# M7106B.net
KiCad netlist of a schematic drawn in EAGLE
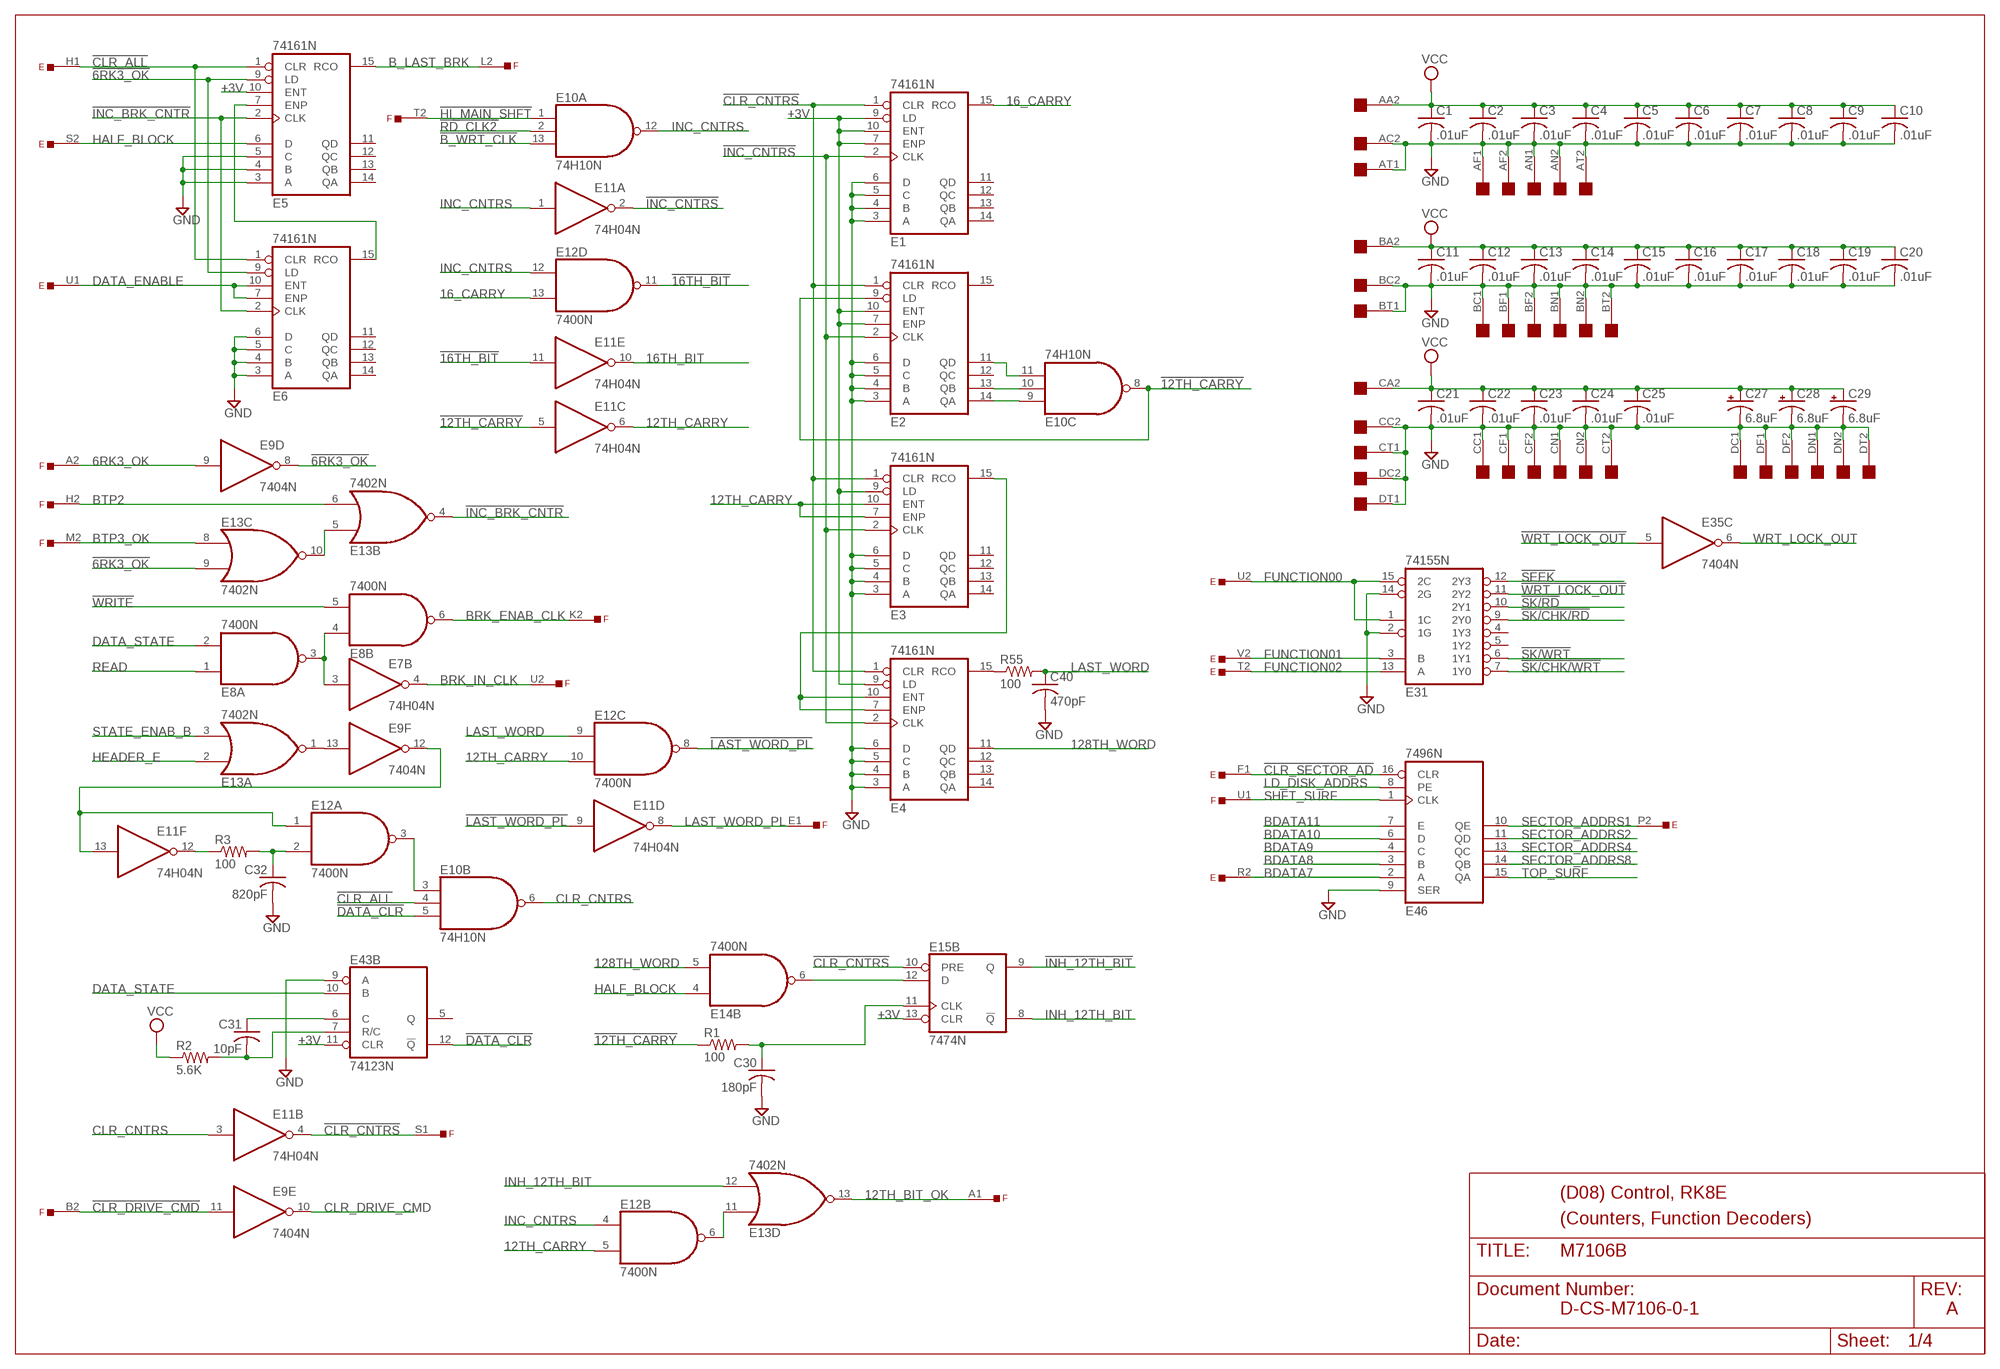
[diagram p0: schematic, sheet 1]
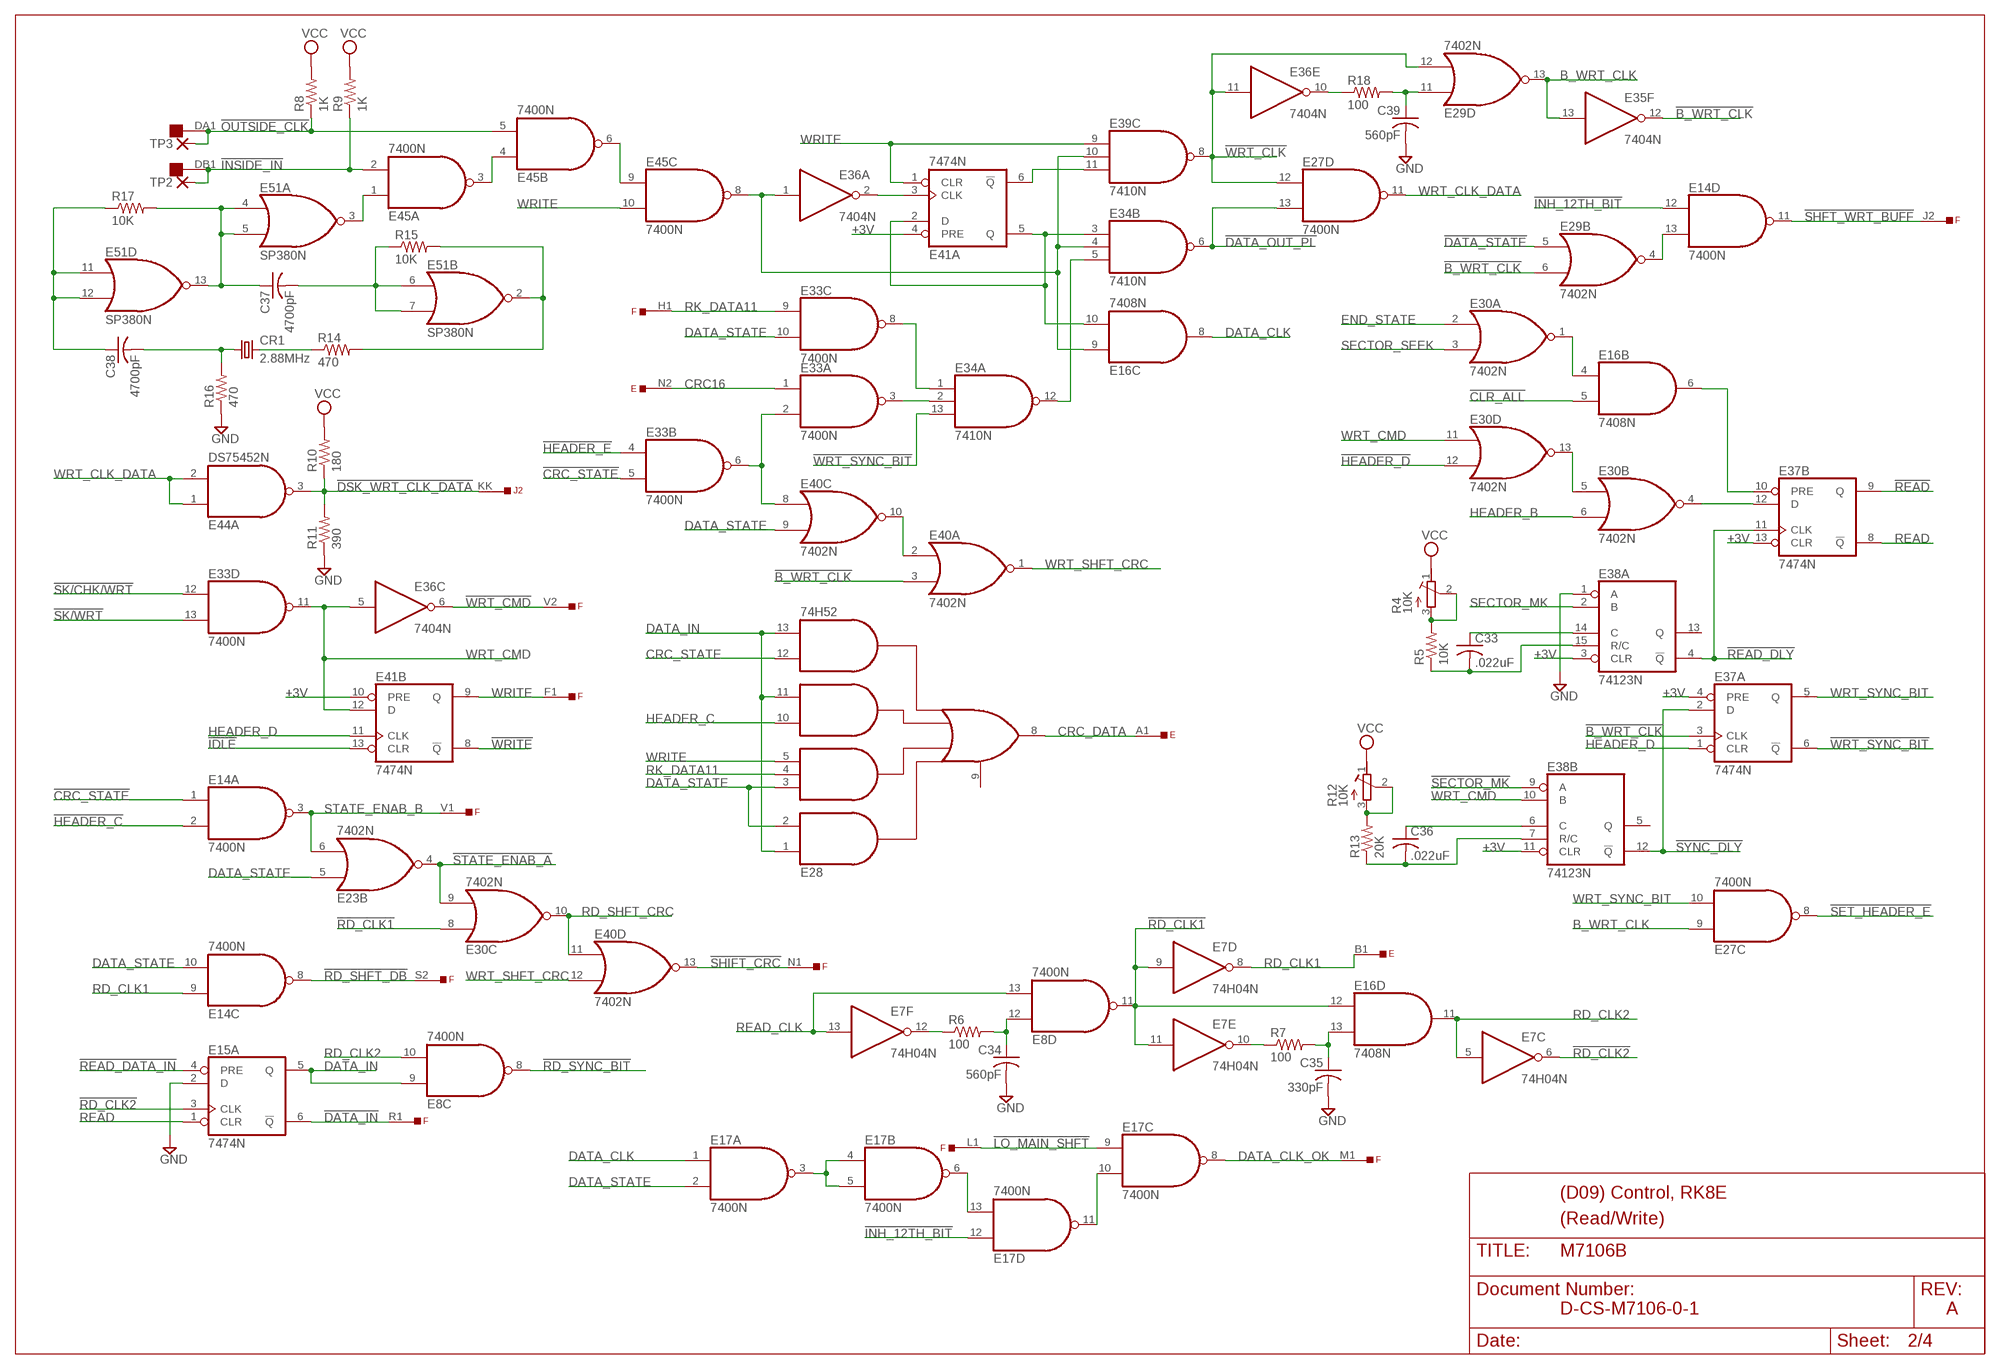
[diagram p1: schematic, sheet 2]
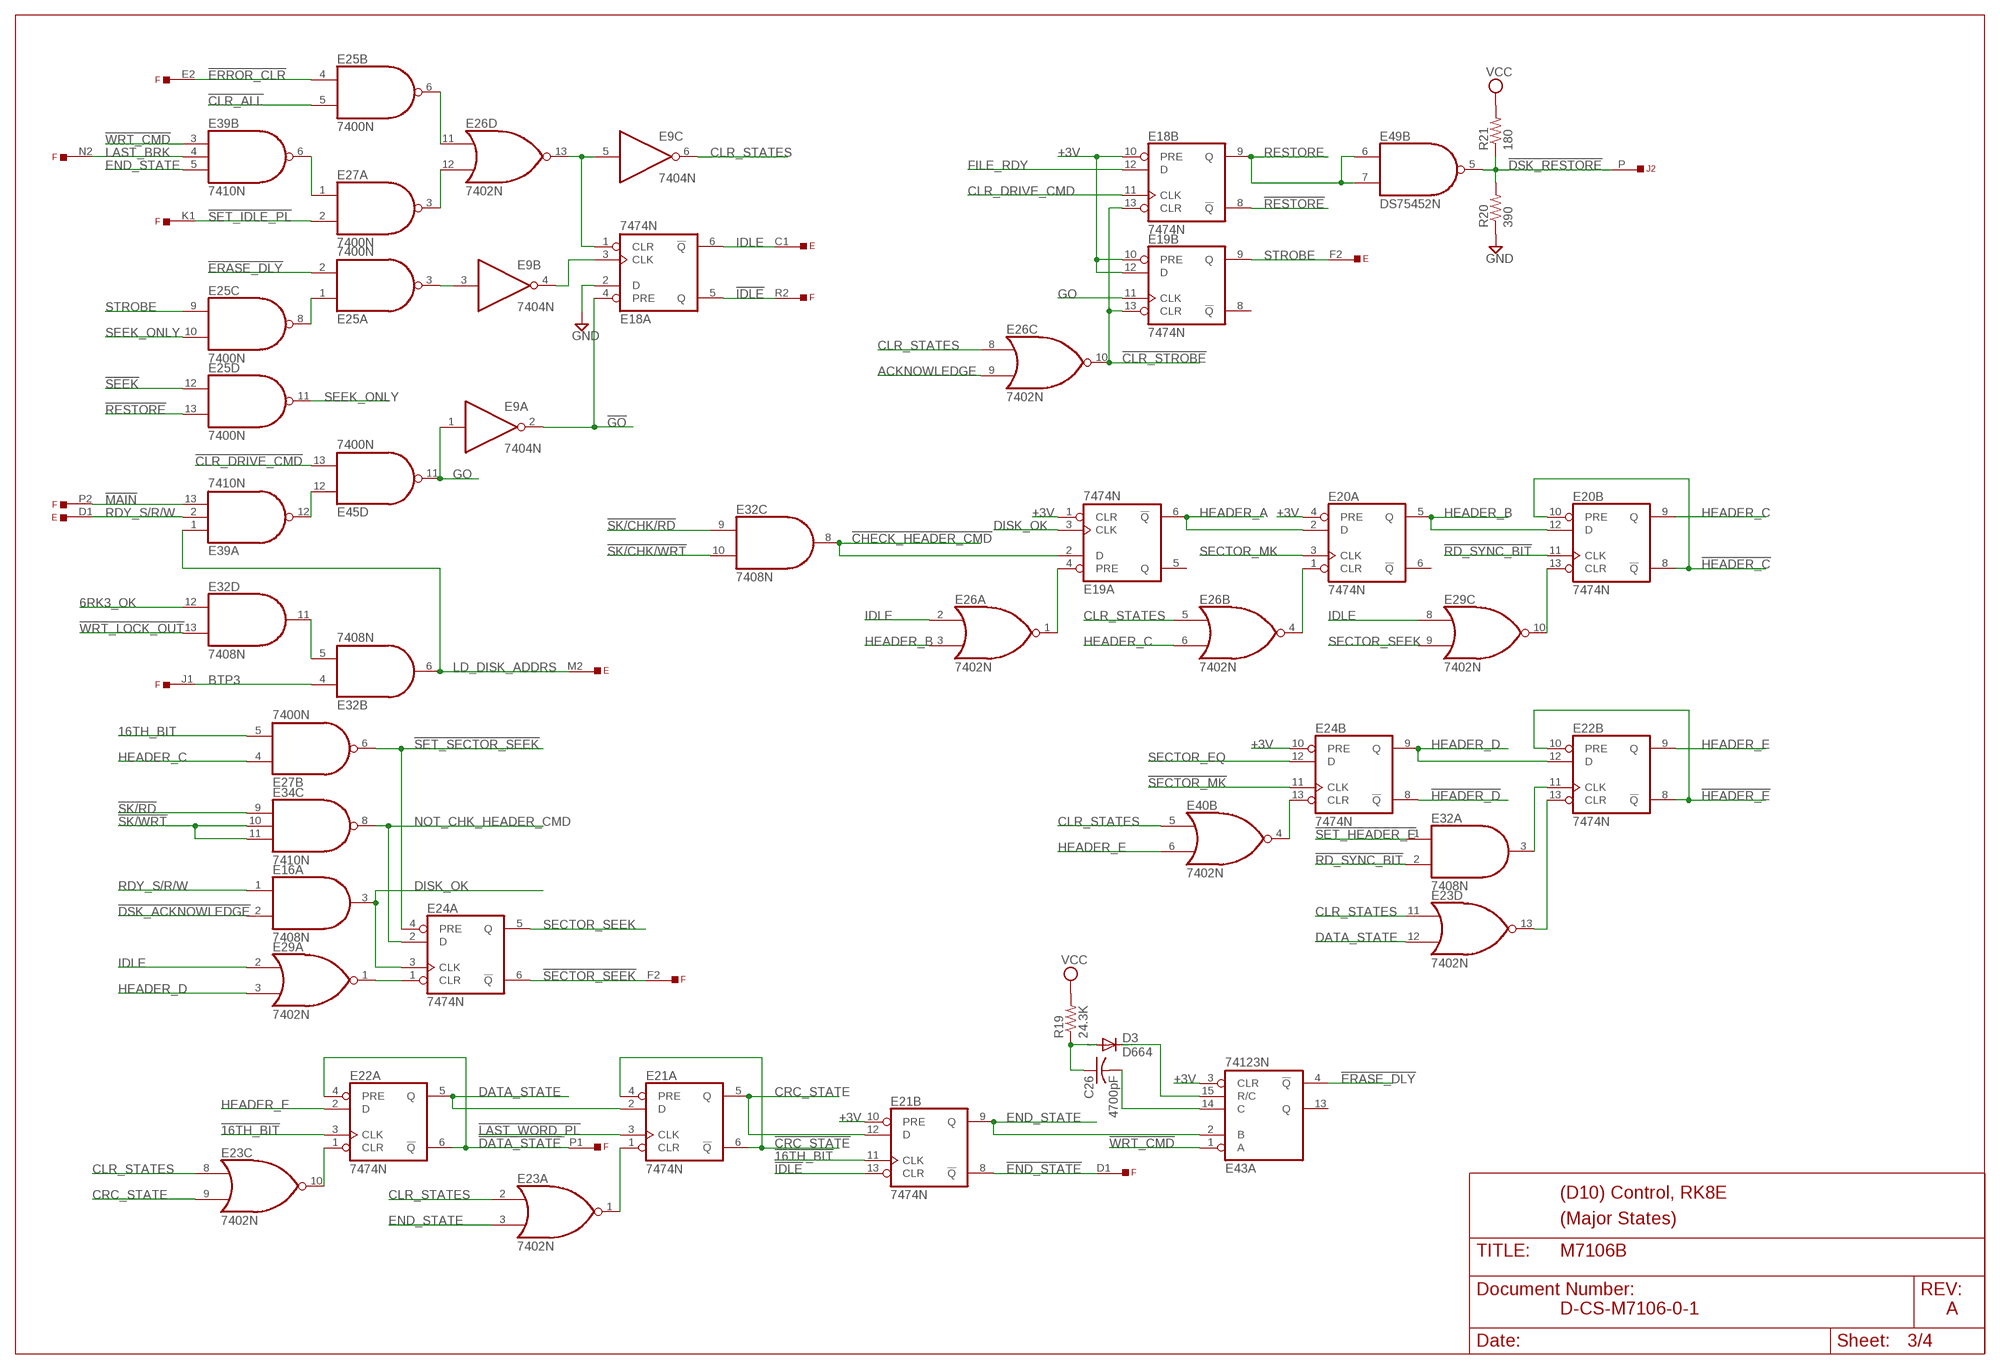
[diagram p2: schematic, sheet 3]
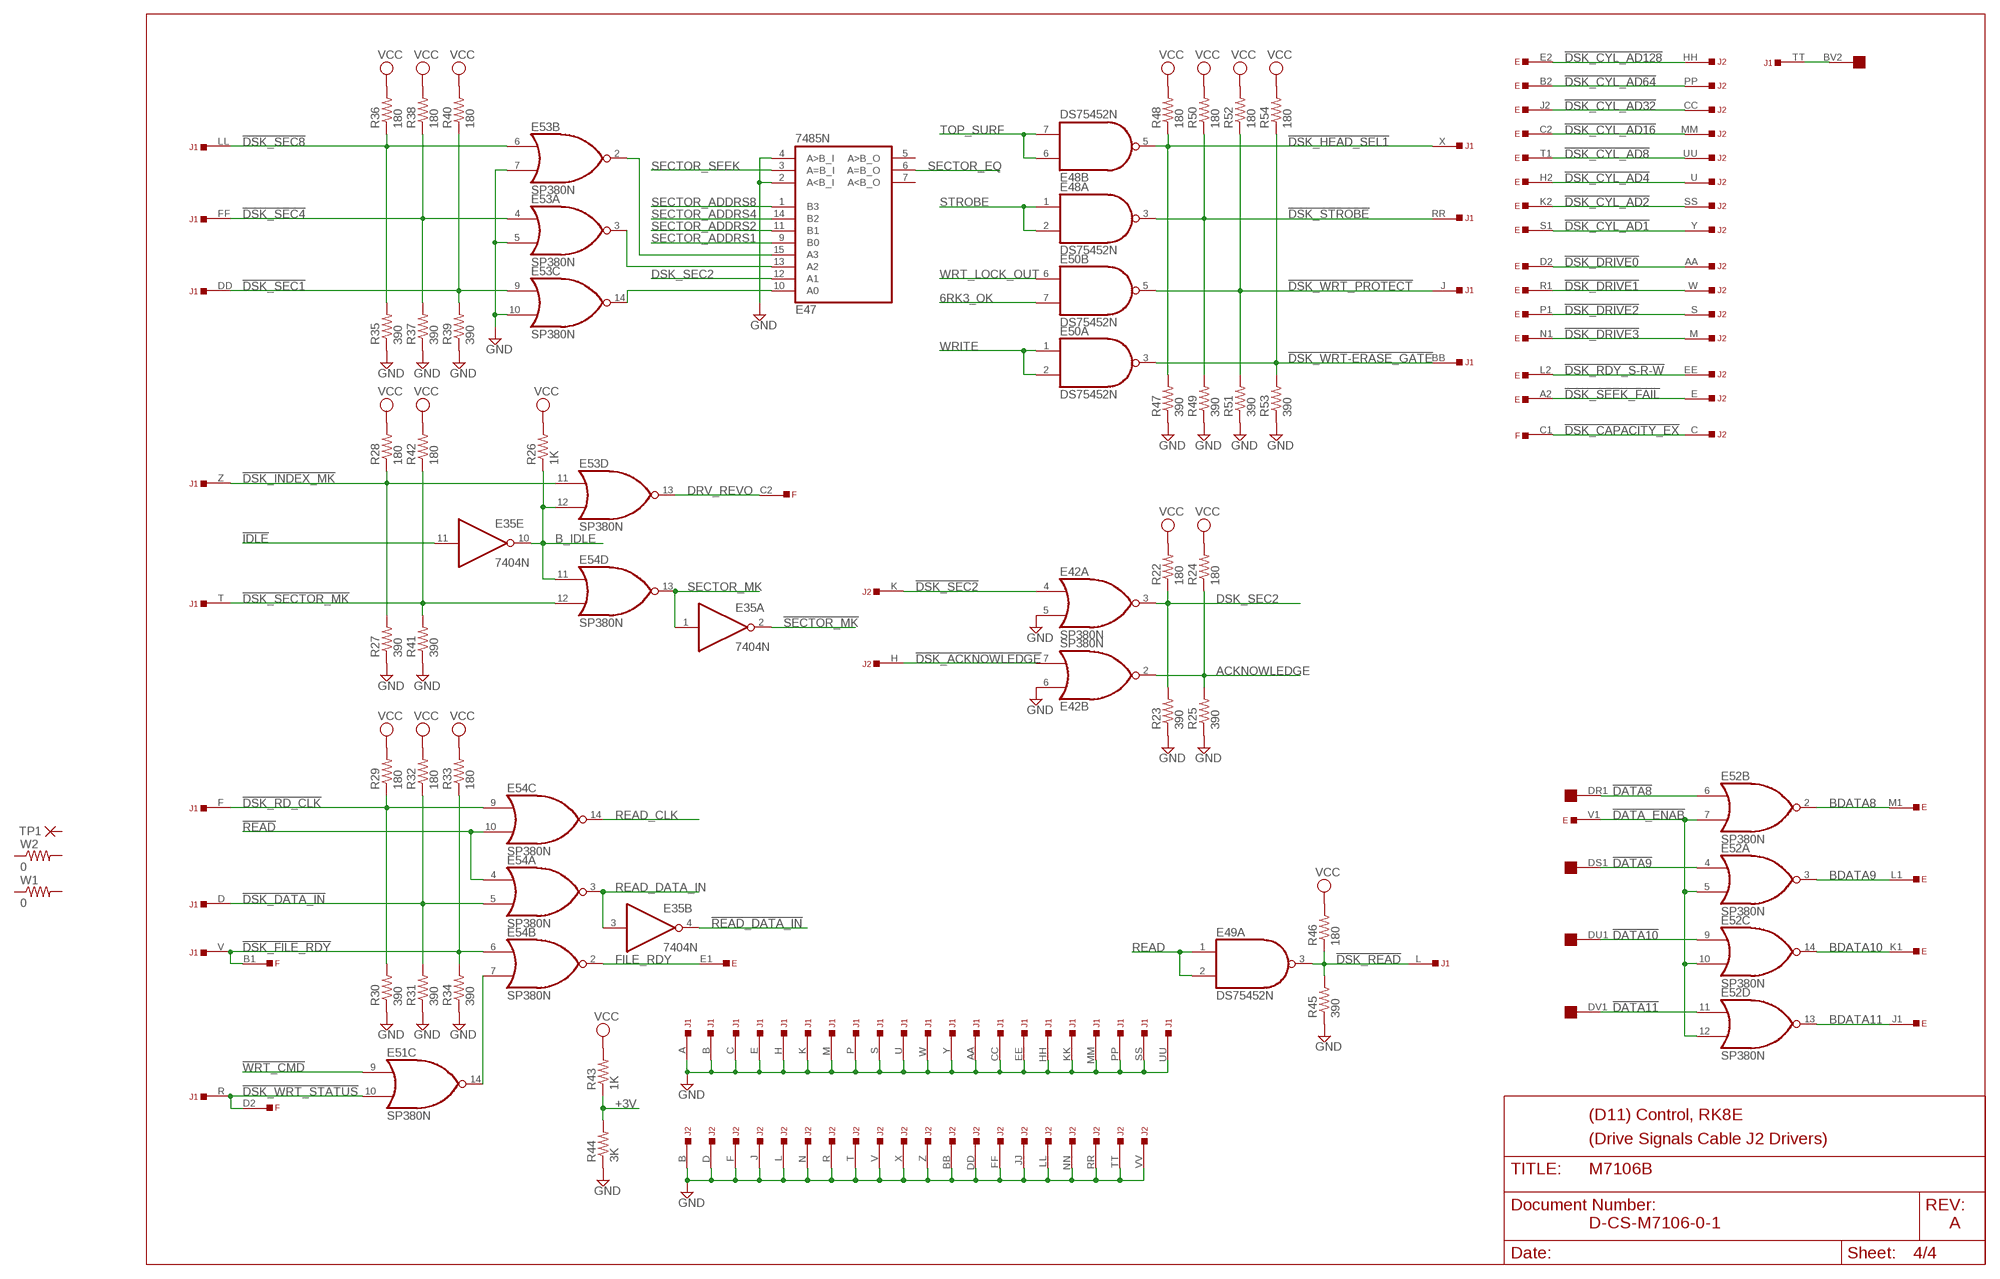
[diagram p3: schematic, sheet 4]

(export (version "E")
  (design (tool "Eeschema 10.0.6"))
  (components
    (comp (ref "C1")
      (value ".01uF")
      (footprint "eagle-import:C063-025X075")
      (libsource (lib "eagle-import") (part "C-US"))
    )
    (comp (ref "C2")
      (value ".01uF")
      (footprint "eagle-import:C063-025X075")
      (libsource (lib "eagle-import") (part "C-US"))
    )
    (comp (ref "C3")
      (value ".01uF")
      (footprint "eagle-import:C063-025X075")
      (libsource (lib "eagle-import") (part "C-US"))
    )
    (comp (ref "C4")
      (value ".01uF")
      (footprint "eagle-import:C063-025X075")
      (libsource (lib "eagle-import") (part "C-US"))
    )
    (comp (ref "C5")
      (value ".01uF")
      (footprint "eagle-import:C063-025X075")
      (libsource (lib "eagle-import") (part "C-US"))
    )
    (comp (ref "C6")
      (value ".01uF")
      (footprint "eagle-import:C063-025X075")
      (libsource (lib "eagle-import") (part "C-US"))
    )
    (comp (ref "C7")
      (value ".01uF")
      (footprint "eagle-import:C063-025X075")
      (libsource (lib "eagle-import") (part "C-US"))
    )
    (comp (ref "C8")
      (value ".01uF")
      (footprint "eagle-import:C063-025X075")
      (libsource (lib "eagle-import") (part "C-US"))
    )
    (comp (ref "C9")
      (value ".01uF")
      (footprint "eagle-import:C063-025X075")
      (libsource (lib "eagle-import") (part "C-US"))
    )
    (comp (ref "C10")
      (value ".01uF")
      (footprint "eagle-import:C063-025X075")
      (libsource (lib "eagle-import") (part "C-US"))
    )
    (comp (ref "C11")
      (value ".01uF")
      (footprint "eagle-import:C063-025X075")
      (libsource (lib "eagle-import") (part "C-US"))
    )
    (comp (ref "C12")
      (value ".01uF")
      (footprint "eagle-import:C063-025X075")
      (libsource (lib "eagle-import") (part "C-US"))
    )
    (comp (ref "C13")
      (value ".01uF")
      (footprint "eagle-import:C063-025X075")
      (libsource (lib "eagle-import") (part "C-US"))
    )
    (comp (ref "C14")
      (value ".01uF")
      (footprint "eagle-import:C063-025X075")
      (libsource (lib "eagle-import") (part "C-US"))
    )
    (comp (ref "C15")
      (value ".01uF")
      (footprint "eagle-import:C063-025X075")
      (libsource (lib "eagle-import") (part "C-US"))
    )
    (comp (ref "C16")
      (value ".01uF")
      (footprint "eagle-import:C063-025X075")
      (libsource (lib "eagle-import") (part "C-US"))
    )
    (comp (ref "C17")
      (value ".01uF")
      (footprint "eagle-import:C063-025X075")
      (libsource (lib "eagle-import") (part "C-US"))
    )
    (comp (ref "C18")
      (value ".01uF")
      (footprint "eagle-import:C063-025X075")
      (libsource (lib "eagle-import") (part "C-US"))
    )
    (comp (ref "C19")
      (value ".01uF")
      (footprint "eagle-import:C063-025X075")
      (libsource (lib "eagle-import") (part "C-US"))
    )
    (comp (ref "C20")
      (value ".01uF")
      (footprint "eagle-import:C063-025X075")
      (libsource (lib "eagle-import") (part "C-US"))
    )
    (comp (ref "C21")
      (value ".01uF")
      (footprint "eagle-import:C063-025X075")
      (libsource (lib "eagle-import") (part "C-US"))
    )
    (comp (ref "C22")
      (value ".01uF")
      (footprint "eagle-import:C063-025X075")
      (libsource (lib "eagle-import") (part "C-US"))
    )
    (comp (ref "C23")
      (value ".01uF")
      (footprint "eagle-import:C063-025X075")
      (libsource (lib "eagle-import") (part "C-US"))
    )
    (comp (ref "C24")
      (value ".01uF")
      (footprint "eagle-import:C063-025X075")
      (libsource (lib "eagle-import") (part "C-US"))
    )
    (comp (ref "C25")
      (value ".01uF")
      (footprint "eagle-import:C063-025X075")
      (libsource (lib "eagle-import") (part "C-US"))
    )
    (comp (ref "C27")
      (value "6.8uF")
      (footprint "eagle-import:E12-8")
      (libsource (lib "eagle-import") (part "CPOL-USE20-8AXIAL"))
    )
    (comp (ref "C28")
      (value "6.8uF")
      (footprint "eagle-import:E12-8")
      (libsource (lib "eagle-import") (part "CPOL-USE20-8AXIAL"))
    )
    (comp (ref "C29")
      (value "6.8uF")
      (footprint "eagle-import:E12-8")
      (libsource (lib "eagle-import") (part "CPOL-USE20-8AXIAL"))
    )
    (comp (ref "C30")
      (value "180pF")
      (footprint "eagle-import:C063-025X075")
      (libsource (lib "eagle-import") (part "C-US"))
    )
    (comp (ref "C31")
      (value "10pF")
      (footprint "eagle-import:C063-025X075")
      (libsource (lib "eagle-import") (part "C-US"))
    )
    (comp (ref "C32")
      (value "820pF")
      (footprint "eagle-import:C063-025X075")
      (libsource (lib "eagle-import") (part "C-US"))
    )
    (comp (ref "C40")
      (value "470pF")
      (footprint "eagle-import:C063-025X075")
      (libsource (lib "eagle-import") (part "C-US"))
    )
    (comp (ref "E")
      (value "EDGE-TOP")
      (footprint "eagle-import:EDGE-CON2")
      (libsource (lib "eagle-import") (part "EDGE-TOP"))
    )
    (comp (ref "E1")
      (value "74161N")
      (footprint "eagle-import:DIL16")
      (libsource (lib "eagle-import") (part "74161N"))
    )
    (comp (ref "E2")
      (value "74161N")
      (footprint "eagle-import:DIL16")
      (libsource (lib "eagle-import") (part "74161N"))
    )
    (comp (ref "E3")
      (value "74161N")
      (footprint "eagle-import:DIL16")
      (libsource (lib "eagle-import") (part "74161N"))
    )
    (comp (ref "E4")
      (value "74161N")
      (footprint "eagle-import:DIL16")
      (libsource (lib "eagle-import") (part "74161N"))
    )
    (comp (ref "E5")
      (value "74161N")
      (footprint "eagle-import:DIL16")
      (libsource (lib "eagle-import") (part "74161N"))
    )
    (comp (ref "E6")
      (value "74161N")
      (footprint "eagle-import:DIL16")
      (libsource (lib "eagle-import") (part "74161N"))
    )
    (comp (ref "E7")
      (value "74H04N")
      (footprint "eagle-import:DIL14")
      (libsource (lib "eagle-import") (part "7404N"))
    )
    (comp (ref "E8")
      (value "7400N")
      (footprint "eagle-import:DIL14")
      (libsource (lib "eagle-import") (part "7400N"))
    )
    (comp (ref "E9")
      (value "7404N")
      (footprint "eagle-import:DIL14")
      (libsource (lib "eagle-import") (part "7404N"))
    )
    (comp (ref "E10")
      (value "74H10N")
      (footprint "eagle-import:DIL14")
      (libsource (lib "eagle-import") (part "7410N"))
    )
    (comp (ref "E11")
      (value "74H04N")
      (footprint "eagle-import:DIL14")
      (libsource (lib "eagle-import") (part "7404N"))
    )
    (comp (ref "E12")
      (value "7400N")
      (footprint "eagle-import:DIL14")
      (libsource (lib "eagle-import") (part "7400N"))
    )
    (comp (ref "E13")
      (value "7402N")
      (footprint "eagle-import:DIL14")
      (libsource (lib "eagle-import") (part "7402N"))
    )
    (comp (ref "E14")
      (value "7400N")
      (footprint "eagle-import:DIL14")
      (libsource (lib "eagle-import") (part "7400N"))
    )
    (comp (ref "E15")
      (value "7474N")
      (footprint "eagle-import:DIL14")
      (libsource (lib "eagle-import") (part "7474NS"))
    )
    (comp (ref "E31")
      (value "74155N")
      (footprint "eagle-import:DIL16")
      (libsource (lib "eagle-import") (part "74155N"))
    )
    (comp (ref "E35")
      (value "7404N")
      (footprint "eagle-import:DIL14")
      (libsource (lib "eagle-import") (part "7404N"))
    )
    (comp (ref "E43")
      (value "74123N")
      (footprint "eagle-import:DIL16")
      (libsource (lib "eagle-import") (part "74123N"))
    )
    (comp (ref "E46")
      (value "7496N")
      (footprint "eagle-import:DIL16")
      (libsource (lib "eagle-import") (part "7496NLS"))
    )
    (comp (ref "F")
      (value "EDGE-TOP")
      (footprint "eagle-import:EDGE-CON2")
      (libsource (lib "eagle-import") (part "EDGE-TOP"))
    )
    (comp (ref "OMNIBUS")
      (value "QUAD")
      (footprint "eagle-import:EDGE-CON8")
      (libsource (lib "eagle-import") (part "QUAD"))
    )
    (comp (ref "R1")
      (value "100")
      (footprint "eagle-import:0207_10")
      (libsource (lib "eagle-import") (part "R-US_0207/10"))
    )
    (comp (ref "R2")
      (value "5.6K")
      (footprint "eagle-import:0207_10")
      (libsource (lib "eagle-import") (part "R-US_0207/10"))
    )
    (comp (ref "R3")
      (value "100")
      (footprint "eagle-import:0207_10")
      (libsource (lib "eagle-import") (part "R-US_0207/10"))
    )
    (comp (ref "R55")
      (value "100")
      (footprint "eagle-import:0207_10")
      (libsource (lib "eagle-import") (part "R-US_0207/10"))
    )
    (comp (ref "C33")
      (value ".022uF")
      (footprint "eagle-import:C203-054-229")
      (libsource (lib "eagle-import") (part "C-US8"))
    )
    (comp (ref "C34")
      (value "560pF")
      (footprint "eagle-import:C063-025X075")
      (libsource (lib "eagle-import") (part "C-US"))
    )
    (comp (ref "C35")
      (value "330pF")
      (footprint "eagle-import:C063-025X075")
      (libsource (lib "eagle-import") (part "C-US"))
    )
    (comp (ref "C36")
      (value ".022uF")
      (footprint "eagle-import:C203-054-229")
      (libsource (lib "eagle-import") (part "C-US8"))
    )
    (comp (ref "C37")
      (value "4700pF")
      (footprint "eagle-import:C203-054-229")
      (libsource (lib "eagle-import") (part "C-US8"))
    )
    (comp (ref "C38")
      (value "4700pF")
      (footprint "eagle-import:C203-054-229")
      (libsource (lib "eagle-import") (part "C-US8"))
    )
    (comp (ref "C39")
      (value "560pF")
      (footprint "eagle-import:C063-025X075")
      (libsource (lib "eagle-import") (part "C-US"))
    )
    (comp (ref "CR1")
      (value "2.88MHz")
      (footprint "eagle-import:HC49TL-H")
      (libsource (lib "eagle-import") (part "CRYSTALHC49TL-H"))
    )
    (comp (ref "E16")
      (value "7408N")
      (footprint "eagle-import:DIL14")
      (libsource (lib "eagle-import") (part "7408NS"))
    )
    (comp (ref "E17")
      (value "7400N")
      (footprint "eagle-import:DIL14")
      (libsource (lib "eagle-import") (part "7400N"))
    )
    (comp (ref "E23")
      (value "7402N")
      (footprint "eagle-import:DIL14")
      (libsource (lib "eagle-import") (part "7402N"))
    )
    (comp (ref "E27")
      (value "7400N")
      (footprint "eagle-import:DIL14")
      (libsource (lib "eagle-import") (part "7400N"))
    )
    (comp (ref "E28")
      (value "74H52")
      (footprint "eagle-import:DIL14")
      (libsource (lib "eagle-import") (part "7452H"))
    )
    (comp (ref "E29")
      (value "7402N")
      (footprint "eagle-import:DIL14")
      (libsource (lib "eagle-import") (part "7402N"))
    )
    (comp (ref "E30")
      (value "7402N")
      (footprint "eagle-import:DIL14")
      (libsource (lib "eagle-import") (part "7402N"))
    )
    (comp (ref "E33")
      (value "7400N")
      (footprint "eagle-import:DIL14")
      (libsource (lib "eagle-import") (part "7400N"))
    )
    (comp (ref "E34")
      (value "7410N")
      (footprint "eagle-import:DIL14")
      (libsource (lib "eagle-import") (part "7410N"))
    )
    (comp (ref "E36")
      (value "7404N")
      (footprint "eagle-import:DIL14")
      (libsource (lib "eagle-import") (part "7404N"))
    )
    (comp (ref "E37")
      (value "7474N")
      (footprint "eagle-import:DIL14")
      (libsource (lib "eagle-import") (part "7474NS"))
    )
    (comp (ref "E38")
      (value "74123N")
      (footprint "eagle-import:DIL16")
      (libsource (lib "eagle-import") (part "74123N"))
    )
    (comp (ref "E39")
      (value "7410N")
      (footprint "eagle-import:DIL14")
      (libsource (lib "eagle-import") (part "7410N"))
    )
    (comp (ref "E40")
      (value "7402N")
      (footprint "eagle-import:DIL14")
      (libsource (lib "eagle-import") (part "7402N"))
    )
    (comp (ref "E41")
      (value "7474N")
      (footprint "eagle-import:DIL14")
      (libsource (lib "eagle-import") (part "7474NS"))
    )
    (comp (ref "E44")
      (value "DS75452N")
      (footprint "eagle-import:DIL08")
      (libsource (lib "eagle-import") (part "DS75452N"))
    )
    (comp (ref "E45")
      (value "7400N")
      (footprint "eagle-import:DIL14")
      (libsource (lib "eagle-import") (part "7400N"))
    )
    (comp (ref "E51")
      (value "SP380N")
      (footprint "eagle-import:DIL14")
      (libsource (lib "eagle-import") (part "SP380N"))
    )
    (comp (ref "J2")
      (value "DEC40PINSH")
      (footprint "eagle-import:DEC40PINH")
      (libsource (lib "eagle-import") (part "DEC40PINSH"))
    )
    (comp (ref "R4")
      (value "10K")
      (footprint "eagle-import:3006Y")
      (libsource (lib "eagle-import") (part "275P"))
    )
    (comp (ref "R5")
      (value "10K")
      (footprint "eagle-import:0207_10")
      (libsource (lib "eagle-import") (part "R-US_0207/10"))
    )
    (comp (ref "R6")
      (value "100")
      (footprint "eagle-import:0207_10")
      (libsource (lib "eagle-import") (part "R-US_0207/10"))
    )
    (comp (ref "R7")
      (value "100")
      (footprint "eagle-import:0207_10")
      (libsource (lib "eagle-import") (part "R-US_0207/10"))
    )
    (comp (ref "R8")
      (value "1K")
      (footprint "eagle-import:0207_10")
      (libsource (lib "eagle-import") (part "R-US_0207/10"))
    )
    (comp (ref "R9")
      (value "1K")
      (footprint "eagle-import:0207_10")
      (libsource (lib "eagle-import") (part "R-US_0207/10"))
    )
    (comp (ref "R10")
      (value "180")
      (footprint "eagle-import:0207_10")
      (libsource (lib "eagle-import") (part "R-US_0207/10"))
    )
    (comp (ref "R11")
      (value "390")
      (footprint "eagle-import:0207_10")
      (libsource (lib "eagle-import") (part "R-US_0207/10"))
    )
    (comp (ref "R12")
      (value "10K")
      (footprint "eagle-import:3006Y")
      (libsource (lib "eagle-import") (part "275P"))
    )
    (comp (ref "R13")
      (value "20K")
      (footprint "eagle-import:0207_10")
      (libsource (lib "eagle-import") (part "R-US_0207/10"))
    )
    (comp (ref "R14")
      (value "470")
      (footprint "eagle-import:0207_10")
      (libsource (lib "eagle-import") (part "R-US_0207/10"))
    )
    (comp (ref "R15")
      (value "10K")
      (footprint "eagle-import:0207_10")
      (libsource (lib "eagle-import") (part "R-US_0207/10"))
    )
    (comp (ref "R16")
      (value "470")
      (footprint "eagle-import:0207_10")
      (libsource (lib "eagle-import") (part "R-US_0207/10"))
    )
    (comp (ref "R17")
      (value "10K")
      (footprint "eagle-import:0207_10")
      (libsource (lib "eagle-import") (part "R-US_0207/10"))
    )
    (comp (ref "R18")
      (value "100")
      (footprint "eagle-import:0207_10")
      (libsource (lib "eagle-import") (part "R-US_0207/10"))
    )
    (comp (ref "TP2")
      (value "PAD-0420")
      (footprint "eagle-import:0420")
      (libsource (lib "eagle-import") (part "PAD-0420"))
    )
    (comp (ref "TP3")
      (value "PAD-0420")
      (footprint "eagle-import:0420")
      (libsource (lib "eagle-import") (part "PAD-0420"))
    )
    (comp (ref "E42")
      (value "SP380N")
      (footprint "eagle-import:DIL14")
      (libsource (lib "eagle-import") (part "SP380N"))
    )
    (comp (ref "E47")
      (value "7485N")
      (footprint "eagle-import:DIL16")
      (libsource (lib "eagle-import") (part "7485N"))
    )
    (comp (ref "E48")
      (value "DS75452N")
      (footprint "eagle-import:DIL08")
      (libsource (lib "eagle-import") (part "DS75452N"))
    )
    (comp (ref "E49")
      (value "DS75452N")
      (footprint "eagle-import:DIL08")
      (libsource (lib "eagle-import") (part "DS75452N"))
    )
    (comp (ref "E50")
      (value "DS75452N")
      (footprint "eagle-import:DIL08")
      (libsource (lib "eagle-import") (part "DS75452N"))
    )
    (comp (ref "E52")
      (value "SP380N")
      (footprint "eagle-import:DIL14")
      (libsource (lib "eagle-import") (part "SP380N"))
    )
    (comp (ref "E53")
      (value "SP380N")
      (footprint "eagle-import:DIL14")
      (libsource (lib "eagle-import") (part "SP380N"))
    )
    (comp (ref "E54")
      (value "SP380N")
      (footprint "eagle-import:DIL14")
      (libsource (lib "eagle-import") (part "SP380N"))
    )
    (comp (ref "J1")
      (value "DEC40PINSH")
      (footprint "eagle-import:DEC40PINH")
      (libsource (lib "eagle-import") (part "DEC40PINSH"))
    )
    (comp (ref "R22")
      (value "180")
      (footprint "eagle-import:0207_10")
      (libsource (lib "eagle-import") (part "R-US_0207/10"))
    )
    (comp (ref "R23")
      (value "390")
      (footprint "eagle-import:0207_10")
      (libsource (lib "eagle-import") (part "R-US_0207/10"))
    )
    (comp (ref "R24")
      (value "180")
      (footprint "eagle-import:0207_10")
      (libsource (lib "eagle-import") (part "R-US_0207/10"))
    )
    (comp (ref "R25")
      (value "390")
      (footprint "eagle-import:0207_10")
      (libsource (lib "eagle-import") (part "R-US_0207/10"))
    )
    (comp (ref "R26")
      (value "1K")
      (footprint "eagle-import:0207_10")
      (libsource (lib "eagle-import") (part "R-US_0207/10"))
    )
    (comp (ref "R27")
      (value "390")
      (footprint "eagle-import:0207_10")
      (libsource (lib "eagle-import") (part "R-US_0207/10"))
    )
    (comp (ref "R28")
      (value "180")
      (footprint "eagle-import:0207_10")
      (libsource (lib "eagle-import") (part "R-US_0207/10"))
    )
    (comp (ref "R29")
      (value "180")
      (footprint "eagle-import:0207_10")
      (libsource (lib "eagle-import") (part "R-US_0207/10"))
    )
    (comp (ref "R30")
      (value "390")
      (footprint "eagle-import:0207_10")
      (libsource (lib "eagle-import") (part "R-US_0207/10"))
    )
    (comp (ref "R31")
      (value "390")
      (footprint "eagle-import:0207_10")
      (libsource (lib "eagle-import") (part "R-US_0207/10"))
    )
    (comp (ref "R32")
      (value "180")
      (footprint "eagle-import:0207_10")
      (libsource (lib "eagle-import") (part "R-US_0207/10"))
    )
    (comp (ref "R33")
      (value "180")
      (footprint "eagle-import:0207_10")
      (libsource (lib "eagle-import") (part "R-US_0207/10"))
    )
    (comp (ref "R34")
      (value "390")
      (footprint "eagle-import:0207_10")
      (libsource (lib "eagle-import") (part "R-US_0207/10"))
    )
    (comp (ref "R35")
      (value "390")
      (footprint "eagle-import:0207_10")
      (libsource (lib "eagle-import") (part "R-US_0207/10"))
    )
    (comp (ref "R36")
      (value "180")
      (footprint "eagle-import:0207_10")
      (libsource (lib "eagle-import") (part "R-US_0207/10"))
    )
    (comp (ref "R37")
      (value "390")
      (footprint "eagle-import:0207_10")
      (libsource (lib "eagle-import") (part "R-US_0207/10"))
    )
    (comp (ref "R38")
      (value "180")
      (footprint "eagle-import:0207_10")
      (libsource (lib "eagle-import") (part "R-US_0207/10"))
    )
    (comp (ref "R39")
      (value "390")
      (footprint "eagle-import:0207_10")
      (libsource (lib "eagle-import") (part "R-US_0207/10"))
    )
    (comp (ref "R40")
      (value "180")
      (footprint "eagle-import:0207_10")
      (libsource (lib "eagle-import") (part "R-US_0207/10"))
    )
    (comp (ref "R41")
      (value "390")
      (footprint "eagle-import:0207_10")
      (libsource (lib "eagle-import") (part "R-US_0207/10"))
    )
    (comp (ref "R42")
      (value "180")
      (footprint "eagle-import:0207_10")
      (libsource (lib "eagle-import") (part "R-US_0207/10"))
    )
    (comp (ref "R43")
      (value "1K")
      (footprint "eagle-import:0207_10")
      (libsource (lib "eagle-import") (part "R-US_0207/10"))
    )
    (comp (ref "R44")
      (value "3K")
      (footprint "eagle-import:0207_10")
      (libsource (lib "eagle-import") (part "R-US_0207/10"))
    )
    (comp (ref "R45")
      (value "390")
      (footprint "eagle-import:0207_10")
      (libsource (lib "eagle-import") (part "R-US_0207/10"))
    )
    (comp (ref "R46")
      (value "180")
      (footprint "eagle-import:0207_10")
      (libsource (lib "eagle-import") (part "R-US_0207/10"))
    )
    (comp (ref "R47")
      (value "390")
      (footprint "eagle-import:0207_10")
      (libsource (lib "eagle-import") (part "R-US_0207/10"))
    )
    (comp (ref "R48")
      (value "180")
      (footprint "eagle-import:0207_10")
      (libsource (lib "eagle-import") (part "R-US_0207/10"))
    )
    (comp (ref "R49")
      (value "390")
      (footprint "eagle-import:0207_10")
      (libsource (lib "eagle-import") (part "R-US_0207/10"))
    )
    (comp (ref "R50")
      (value "180")
      (footprint "eagle-import:0207_10")
      (libsource (lib "eagle-import") (part "R-US_0207/10"))
    )
    (comp (ref "R51")
      (value "390")
      (footprint "eagle-import:0207_10")
      (libsource (lib "eagle-import") (part "R-US_0207/10"))
    )
    (comp (ref "R52")
      (value "180")
      (footprint "eagle-import:0207_10")
      (libsource (lib "eagle-import") (part "R-US_0207/10"))
    )
    (comp (ref "R53")
      (value "390")
      (footprint "eagle-import:0207_10")
      (libsource (lib "eagle-import") (part "R-US_0207/10"))
    )
    (comp (ref "R54")
      (value "180")
      (footprint "eagle-import:0207_10")
      (libsource (lib "eagle-import") (part "R-US_0207/10"))
    )
    (comp (ref "TP1")
      (value "PAD-0420")
      (footprint "eagle-import:0420")
      (libsource (lib "eagle-import") (part "PAD-0420"))
    )
    (comp (ref "W1")
      (value "0")
      (footprint "eagle-import:0207_10")
      (libsource (lib "eagle-import") (part "R-US_0207/10"))
    )
    (comp (ref "W2")
      (value "0")
      (footprint "eagle-import:0207_10")
      (libsource (lib "eagle-import") (part "R-US_0207/10"))
    )
    (comp (ref "C26")
      (value "4700pF")
      (footprint "eagle-import:C203-054-229")
      (libsource (lib "eagle-import") (part "C-US8"))
    )
    (comp (ref "D3")
      (value "D664")
      (footprint "eagle-import:DO35-10")
      (libsource (lib "eagle-import") (part "DIODE-DO35-10"))
    )
    (comp (ref "E18")
      (value "7474N")
      (footprint "eagle-import:DIL14")
      (libsource (lib "eagle-import") (part "7474NS"))
    )
    (comp (ref "E19")
      (value "7474N")
      (footprint "eagle-import:DIL14")
      (libsource (lib "eagle-import") (part "7474NS"))
    )
    (comp (ref "E20")
      (value "7474N")
      (footprint "eagle-import:DIL14")
      (libsource (lib "eagle-import") (part "7474NS"))
    )
    (comp (ref "E21")
      (value "7474N")
      (footprint "eagle-import:DIL14")
      (libsource (lib "eagle-import") (part "7474NS"))
    )
    (comp (ref "E22")
      (value "7474N")
      (footprint "eagle-import:DIL14")
      (libsource (lib "eagle-import") (part "7474NS"))
    )
    (comp (ref "E24")
      (value "7474N")
      (footprint "eagle-import:DIL14")
      (libsource (lib "eagle-import") (part "7474NS"))
    )
    (comp (ref "E25")
      (value "7400N")
      (footprint "eagle-import:DIL14")
      (libsource (lib "eagle-import") (part "7400NS"))
    )
    (comp (ref "E26")
      (value "7402N")
      (footprint "eagle-import:DIL14")
      (libsource (lib "eagle-import") (part "7402N"))
    )
    (comp (ref "E32")
      (value "7408N")
      (footprint "eagle-import:DIL14")
      (libsource (lib "eagle-import") (part "7408NS"))
    )
    (comp (ref "R19")
      (value "24.3K")
      (footprint "eagle-import:0207_15")
      (libsource (lib "eagle-import") (part "R-US_0207/15"))
    )
    (comp (ref "R20")
      (value "390")
      (footprint "eagle-import:0207_10")
      (libsource (lib "eagle-import") (part "R-US_0207/10"))
    )
    (comp (ref "R21")
      (value "180")
      (footprint "eagle-import:0207_10")
      (libsource (lib "eagle-import") (part "R-US_0207/10"))
    )
  )
  (nets
    (net (code "1") (name "+3V") (class "Default")
      (node (ref "E1") (pin "10") (pinfunction "ENT_10") (pintype "input"))
      (node (ref "E1") (pin "7") (pinfunction "ENP_7") (pintype "input"))
      (node (ref "E1") (pin "9") (pinfunction "LD_9") (pintype "input"))
      (node (ref "E15") (pin "13") (pinfunction "CLR_13") (pintype "input"))
      (node (ref "E18") (pin "10") (pinfunction "PRE_10") (pintype "input"))
      (node (ref "E19") (pin "1") (pinfunction "CLR_1") (pintype "input"))
      (node (ref "E19") (pin "10") (pinfunction "PRE_10") (pintype "input"))
      (node (ref "E19") (pin "12") (pinfunction "D_12") (pintype "input"))
      (node (ref "E2") (pin "10") (pinfunction "ENT_10") (pintype "input"))
      (node (ref "E2") (pin "7") (pinfunction "ENP_7") (pintype "input"))
      (node (ref "E20") (pin "4") (pinfunction "PRE_4") (pintype "input"))
      (node (ref "E21") (pin "10") (pinfunction "PRE_10") (pintype "input"))
      (node (ref "E24") (pin "10") (pinfunction "PRE_10") (pintype "input"))
      (node (ref "E3") (pin "9") (pinfunction "LD_9") (pintype "input"))
      (node (ref "E37") (pin "13") (pinfunction "CLR_13") (pintype "input"))
      (node (ref "E37") (pin "4") (pinfunction "PRE_4") (pintype "input"))
      (node (ref "E38") (pin "11") (pinfunction "CLR_11") (pintype "input"))
      (node (ref "E38") (pin "3") (pinfunction "CLR_3") (pintype "input"))
      (node (ref "E4") (pin "9") (pinfunction "LD_9") (pintype "input"))
      (node (ref "E41") (pin "10") (pinfunction "PRE_10") (pintype "input"))
      (node (ref "E41") (pin "4") (pinfunction "PRE_4") (pintype "input"))
      (node (ref "E43") (pin "11") (pinfunction "CLR_11") (pintype "input"))
      (node (ref "E43") (pin "3") (pinfunction "CLR_3") (pintype "input"))
      (node (ref "E5") (pin "10") (pinfunction "ENT_10") (pintype "input"))
      (node (ref "R43") (pin "1") (pinfunction "1_1") (pintype "passive"))
      (node (ref "R44") (pin "2") (pinfunction "2_2") (pintype "passive"))
    )
    (net (code "2") (name "6RK3_OK") (class "Default")
      (node (ref "E32") (pin "12") (pinfunction "I0_12") (pintype "input"))
      (node (ref "E50") (pin "7") (pinfunction "I1_7") (pintype "input"))
      (node (ref "E9") (pin "9") (pinfunction "I_9") (pintype "input"))
      (node (ref "F") (pin "A2") (pinfunction "P_A2") (pintype "passive"))
    )
    (net (code "3") (name "12TH_BIT_OK") (class "Default")
      (node (ref "E13") (pin "13") (pinfunction "O_13") (pintype "output"))
      (node (ref "F") (pin "A1") (pinfunction "P_A1") (pintype "passive"))
    )
    (net (code "4") (name "12TH_CARRY") (class "Default")
      (node (ref "E11") (pin "6") (pinfunction "O_6") (pintype "output"))
      (node (ref "E12") (pin "10") (pinfunction "I1_10") (pintype "input"))
      (node (ref "E12") (pin "5") (pinfunction "I1_5") (pintype "input"))
      (node (ref "E3") (pin "10") (pinfunction "ENT_10") (pintype "input"))
      (node (ref "E3") (pin "7") (pinfunction "ENP_7") (pintype "input"))
    )
    (net (code "5") (name "16TH_BIT") (class "Default")
      (node (ref "E11") (pin "10") (pinfunction "O_10") (pintype "output"))
      (node (ref "E27") (pin "5") (pinfunction "I1_5") (pintype "input"))
    )
    (net (code "6") (name "16_CARRY") (class "Default")
      (node (ref "E1") (pin "15") (pinfunction "RCO_15") (pintype "output"))
      (node (ref "E12") (pin "13") (pinfunction "I1_13") (pintype "input"))
    )
    (net (code "7") (name "128TH_WORD") (class "Default")
      (node (ref "E14") (pin "5") (pinfunction "I1_5") (pintype "input"))
      (node (ref "E4") (pin "11") (pinfunction "QD_11") (pintype "output"))
    )
    (net (code "8") (name "ACKNOWLEDGE") (class "Default")
      (node (ref "E26") (pin "9") (pinfunction "I1_9") (pintype "input"))
      (node (ref "E42") (pin "2") (pinfunction "O_2") (pintype "output"))
      (node (ref "R24") (pin "1") (pinfunction "1_1") (pintype "passive"))
      (node (ref "R25") (pin "2") (pinfunction "2_2") (pintype "passive"))
    )
    (net (code "9") (name "BDATA7") (class "Default")
      (node (ref "E") (pin "R2") (pinfunction "P_R2") (pintype "passive"))
      (node (ref "E46") (pin "2") (pinfunction "A_2") (pintype "input"))
    )
    (net (code "10") (name "BDATA8") (class "Default")
      (node (ref "E") (pin "M1") (pinfunction "P_M1") (pintype "passive"))
      (node (ref "E46") (pin "3") (pinfunction "B_3") (pintype "input"))
      (node (ref "E52") (pin "2") (pinfunction "O_2") (pintype "output"))
    )
    (net (code "11") (name "BDATA9") (class "Default")
      (node (ref "E") (pin "L1") (pinfunction "P_L1") (pintype "passive"))
      (node (ref "E46") (pin "4") (pinfunction "C_4") (pintype "input"))
      (node (ref "E52") (pin "3") (pinfunction "O_3") (pintype "output"))
    )
    (net (code "12") (name "BDATA10") (class "Default")
      (node (ref "E") (pin "K1") (pinfunction "P_K1") (pintype "passive"))
      (node (ref "E46") (pin "6") (pinfunction "D_6") (pintype "input"))
      (node (ref "E52") (pin "14") (pinfunction "O_14") (pintype "output"))
    )
    (net (code "13") (name "BDATA11") (class "Default")
      (node (ref "E") (pin "J1") (pinfunction "P_J1") (pintype "passive"))
      (node (ref "E46") (pin "7") (pinfunction "E_7") (pintype "input"))
      (node (ref "E52") (pin "13") (pinfunction "O_13") (pintype "output"))
    )
    (net (code "14") (name "BRK_ENAB_CLK") (class "Default")
      (node (ref "E8") (pin "6") (pinfunction "O_6") (pintype "output"))
      (node (ref "F") (pin "K2") (pinfunction "P_K2") (pintype "passive"))
    )
    (net (code "15") (name "BRK_IN_CLK") (class "Default")
      (node (ref "E7") (pin "4") (pinfunction "O_4") (pintype "output"))
      (node (ref "F") (pin "U2") (pinfunction "P_U2") (pintype "passive"))
    )
    (net (code "16") (name "BTP2") (class "Default")
      (node (ref "E13") (pin "6") (pinfunction "I1_6") (pintype "input"))
      (node (ref "F") (pin "H2") (pinfunction "P_H2") (pintype "passive"))
    )
    (net (code "17") (name "BTP3") (class "Default")
      (node (ref "E32") (pin "4") (pinfunction "I0_4") (pintype "input"))
      (node (ref "F") (pin "J1") (pinfunction "P_J1") (pintype "passive"))
    )
    (net (code "18") (name "BTP3_OK") (class "Default")
      (node (ref "E13") (pin "8") (pinfunction "I0_8") (pintype "input"))
      (node (ref "F") (pin "M2") (pinfunction "P_M2") (pintype "passive"))
    )
    (net (code "19") (name "B_IDLE") (class "Default")
      (node (ref "E35") (pin "10") (pinfunction "O_10") (pintype "output"))
      (node (ref "E53") (pin "12") (pinfunction "I1_12") (pintype "input"))
      (node (ref "E54") (pin "11") (pinfunction "I0_11") (pintype "input"))
      (node (ref "R26") (pin "1") (pinfunction "1_1") (pintype "passive"))
    )
    (net (code "20") (name "B_LAST_BRK") (class "Default")
      (node (ref "E5") (pin "15") (pinfunction "RCO_15") (pintype "output"))
      (node (ref "F") (pin "L2") (pinfunction "P_L2") (pintype "passive"))
    )
    (net (code "21") (name "B_WRT_CLK") (class "Default")
      (node (ref "E27") (pin "9") (pinfunction "I0_9") (pintype "input"))
      (node (ref "E29") (pin "13") (pinfunction "O_13") (pintype "output"))
      (node (ref "E35") (pin "13") (pinfunction "I_13") (pintype "input"))
    )
    (net (code "22") (name "CLR_CNTRS") (class "Default")
      (node (ref "E10") (pin "6") (pinfunction "O_6") (pintype "output"))
      (node (ref "E11") (pin "3") (pinfunction "I_3") (pintype "input"))
    )
    (net (code "23") (name "CLR_DRIVE_CMD") (class "Default")
      (node (ref "E18") (pin "11") (pinfunction "CLK_11") (pintype "input"))
      (node (ref "E9") (pin "10") (pinfunction "O_10") (pintype "output"))
    )
    (net (code "24") (name "CLR_STATES") (class "Default")
      (node (ref "E23") (pin "11") (pinfunction "I0_11") (pintype "input"))
      (node (ref "E23") (pin "2") (pinfunction "I0_2") (pintype "input"))
      (node (ref "E23") (pin "8") (pinfunction "I0_8") (pintype "input"))
      (node (ref "E26") (pin "5") (pinfunction "I0_5") (pintype "input"))
      (node (ref "E26") (pin "8") (pinfunction "I0_8") (pintype "input"))
      (node (ref "E40") (pin "5") (pinfunction "I0_5") (pintype "input"))
      (node (ref "E9") (pin "6") (pinfunction "O_6") (pintype "output"))
    )
    (net (code "25") (name "CRC16") (class "Default")
      (node (ref "E") (pin "N2") (pinfunction "P_N2") (pintype "passive"))
      (node (ref "E33") (pin "1") (pinfunction "I0_1") (pintype "input"))
    )
    (net (code "26") (name "CRC_DATA") (class "Default")
      (node (ref "E") (pin "A1") (pinfunction "P_A1") (pintype "passive"))
      (node (ref "E28") (pin "8") (pinfunction "O8_8") (pintype "output"))
    )
    (net (code "27") (name "CRC_STATE") (class "Default")
      (node (ref "E21") (pin "12") (pinfunction "D_12") (pintype "input"))
      (node (ref "E21") (pin "5") (pinfunction "Q_5") (pintype "output"))
      (node (ref "E23") (pin "9") (pinfunction "I1_9") (pintype "input"))
      (node (ref "E28") (pin "12") (pinfunction "I12_12") (pintype "input"))
    )
    (net (code "28") (name "DATA_CLK") (class "Default")
      (node (ref "E16") (pin "8") (pinfunction "O_8") (pintype "output"))
      (node (ref "E17") (pin "1") (pinfunction "I0_1") (pintype "input"))
    )
    (net (code "29") (name "DATA_CLK_OK") (class "Default")
      (node (ref "E17") (pin "8") (pinfunction "O_8") (pintype "output"))
      (node (ref "F") (pin "M1") (pinfunction "P_M1") (pintype "passive"))
    )
    (net (code "30") (name "DATA_ENABLE") (class "Default")
      (node (ref "E") (pin "U1") (pinfunction "P_U1") (pintype "passive"))
      (node (ref "E6") (pin "10") (pinfunction "ENT_10") (pintype "input"))
      (node (ref "E6") (pin "7") (pinfunction "ENP_7") (pintype "input"))
    )
    (net (code "31") (name "DATA_IN") (class "Default")
      (node (ref "E15") (pin "5") (pinfunction "Q_5") (pintype "output"))
      (node (ref "E28") (pin "1") (pinfunction "I1_1") (pintype "input"))
      (node (ref "E28") (pin "11") (pinfunction "I11_11") (pintype "input"))
      (node (ref "E28") (pin "13") (pinfunction "I13_13") (pintype "input"))
      (node (ref "E8") (pin "9") (pinfunction "I0_9") (pintype "input"))
    )
    (net (code "32") (name "DATA_STATE") (class "Default")
      (node (ref "E14") (pin "10") (pinfunction "I1_10") (pintype "input"))
      (node (ref "E17") (pin "2") (pinfunction "I1_2") (pintype "input"))
      (node (ref "E21") (pin "2") (pinfunction "D_2") (pintype "input"))
      (node (ref "E22") (pin "5") (pinfunction "Q_5") (pintype "output"))
      (node (ref "E23") (pin "12") (pinfunction "I1_12") (pintype "input"))
      (node (ref "E23") (pin "5") (pinfunction "I0_5") (pintype "input"))
      (node (ref "E28") (pin "2") (pinfunction "I2_2") (pintype "input"))
      (node (ref "E28") (pin "3") (pinfunction "I3_3") (pintype "input"))
      (node (ref "E33") (pin "10") (pinfunction "I1_10") (pintype "input"))
      (node (ref "E40") (pin "9") (pinfunction "I1_9") (pintype "input"))
      (node (ref "E43") (pin "10") (pinfunction "B_10") (pintype "input"))
      (node (ref "E8") (pin "2") (pinfunction "I1_2") (pintype "input"))
    )
    (net (code "33") (name "DISK_OK") (class "Default")
      (node (ref "E16") (pin "3") (pinfunction "O_3") (pintype "output"))
      (node (ref "E19") (pin "3") (pinfunction "CLK_3") (pintype "input"))
      (node (ref "E24") (pin "3") (pinfunction "CLK_3") (pintype "input"))
    )
    (net (code "34") (name "DRV_REVO") (class "Default")
      (node (ref "E53") (pin "13") (pinfunction "O_13") (pintype "output"))
      (node (ref "F") (pin "C2") (pinfunction "P_C2") (pintype "passive"))
    )
    (net (code "35") (name "DSK_SEC2") (class "Default")
      (node (ref "E42") (pin "3") (pinfunction "O_3") (pintype "output"))
      (node (ref "E47") (pin "12") (pinfunction "A1_12") (pintype "input"))
      (node (ref "R22") (pin "1") (pinfunction "1_1") (pintype "passive"))
      (node (ref "R23") (pin "2") (pinfunction "2_2") (pintype "passive"))
    )
    (net (code "36") (name "END_STATE") (class "Default")
      (node (ref "E21") (pin "9") (pinfunction "Q_9") (pintype "output"))
      (node (ref "E23") (pin "3") (pinfunction "I1_3") (pintype "input"))
      (node (ref "E30") (pin "2") (pinfunction "I0_2") (pintype "input"))
      (node (ref "E39") (pin "5") (pinfunction "I2_5") (pintype "input"))
      (node (ref "E43") (pin "2") (pinfunction "B_2") (pintype "input"))
    )
    (net (code "37") (name "FILE_RDY") (class "Default")
      (node (ref "E") (pin "E1") (pinfunction "P_E1") (pintype "passive"))
      (node (ref "E18") (pin "12") (pinfunction "D_12") (pintype "input"))
      (node (ref "E54") (pin "2") (pinfunction "O_2") (pintype "output"))
    )
    (net (code "38") (name "FUNCTION00") (class "Default")
      (node (ref "E") (pin "U2") (pinfunction "P_U2") (pintype "passive"))
      (node (ref "E31") (pin "1") (pinfunction "1C_1") (pintype "input"))
      (node (ref "E31") (pin "15") (pinfunction "2C_15") (pintype "input"))
    )
    (net (code "39") (name "FUNCTION01") (class "Default")
      (node (ref "E") (pin "V2") (pinfunction "P_V2") (pintype "passive"))
      (node (ref "E31") (pin "3") (pinfunction "B_3") (pintype "input"))
    )
    (net (code "40") (name "FUNCTION02") (class "Default")
      (node (ref "E") (pin "T2") (pinfunction "P_T2") (pintype "passive"))
      (node (ref "E31") (pin "13") (pinfunction "A_13") (pintype "input"))
    )
    (net (code "41") (name "GND") (class "Default")
      (node (ref "C1") (pin "2") (pinfunction "2_2") (pintype "passive"))
      (node (ref "C10") (pin "2") (pinfunction "2_2") (pintype "passive"))
      (node (ref "C11") (pin "2") (pinfunction "2_2") (pintype "passive"))
      (node (ref "C12") (pin "2") (pinfunction "2_2") (pintype "passive"))
      (node (ref "C13") (pin "2") (pinfunction "2_2") (pintype "passive"))
      (node (ref "C14") (pin "2") (pinfunction "2_2") (pintype "passive"))
      (node (ref "C15") (pin "2") (pinfunction "2_2") (pintype "passive"))
      (node (ref "C16") (pin "2") (pinfunction "2_2") (pintype "passive"))
      (node (ref "C17") (pin "2") (pinfunction "2_2") (pintype "passive"))
      (node (ref "C18") (pin "2") (pinfunction "2_2") (pintype "passive"))
      (node (ref "C19") (pin "2") (pinfunction "2_2") (pintype "passive"))
      (node (ref "C2") (pin "2") (pinfunction "2_2") (pintype "passive"))
      (node (ref "C20") (pin "2") (pinfunction "2_2") (pintype "passive"))
      (node (ref "C21") (pin "2") (pinfunction "2_2") (pintype "passive"))
      (node (ref "C22") (pin "2") (pinfunction "2_2") (pintype "passive"))
      (node (ref "C23") (pin "2") (pinfunction "2_2") (pintype "passive"))
      (node (ref "C24") (pin "2") (pinfunction "2_2") (pintype "passive"))
      (node (ref "C25") (pin "2") (pinfunction "2_2") (pintype "passive"))
      (node (ref "C27") (pin "-") (pinfunction "-_-") (pintype "passive"))
      (node (ref "C28") (pin "-") (pinfunction "-_-") (pintype "passive"))
      (node (ref "C29") (pin "-") (pinfunction "-_-") (pintype "passive"))
      (node (ref "C3") (pin "2") (pinfunction "2_2") (pintype "passive"))
      (node (ref "C30") (pin "2") (pinfunction "2_2") (pintype "passive"))
      (node (ref "C32") (pin "2") (pinfunction "2_2") (pintype "passive"))
      (node (ref "C34") (pin "2") (pinfunction "2_2") (pintype "passive"))
      (node (ref "C35") (pin "2") (pinfunction "2_2") (pintype "passive"))
      (node (ref "C39") (pin "2") (pinfunction "2_2") (pintype "passive"))
      (node (ref "C4") (pin "2") (pinfunction "2_2") (pintype "passive"))
      (node (ref "C40") (pin "2") (pinfunction "2_2") (pintype "passive"))
      (node (ref "C5") (pin "2") (pinfunction "2_2") (pintype "passive"))
      (node (ref "C6") (pin "2") (pinfunction "2_2") (pintype "passive"))
      (node (ref "C7") (pin "2") (pinfunction "2_2") (pintype "passive"))
      (node (ref "C8") (pin "2") (pinfunction "2_2") (pintype "passive"))
      (node (ref "C9") (pin "2") (pinfunction "2_2") (pintype "passive"))
      (node (ref "E1") (pin "3") (pinfunction "A_3") (pintype "input"))
      (node (ref "E1") (pin "4") (pinfunction "B_4") (pintype "input"))
      (node (ref "E1") (pin "5") (pinfunction "C_5") (pintype "input"))
      (node (ref "E1") (pin "6") (pinfunction "D_6") (pintype "input"))
      (node (ref "E15") (pin "2") (pinfunction "D_2") (pintype "input"))
      (node (ref "E18") (pin "2") (pinfunction "D_2") (pintype "input"))
      (node (ref "E2") (pin "3") (pinfunction "A_3") (pintype "input"))
      (node (ref "E2") (pin "4") (pinfunction "B_4") (pintype "input"))
      (node (ref "E2") (pin "5") (pinfunction "C_5") (pintype "input"))
      (node (ref "E2") (pin "6") (pinfunction "D_6") (pintype "input"))
      (node (ref "E3") (pin "3") (pinfunction "A_3") (pintype "input"))
      (node (ref "E3") (pin "4") (pinfunction "B_4") (pintype "input"))
      (node (ref "E3") (pin "5") (pinfunction "C_5") (pintype "input"))
      (node (ref "E3") (pin "6") (pinfunction "D_6") (pintype "input"))
      (node (ref "E31") (pin "14") (pinfunction "2G_14") (pintype "input"))
      (node (ref "E31") (pin "2") (pinfunction "1G_2") (pintype "input"))
      (node (ref "E38") (pin "1") (pinfunction "A_1") (pintype "input"))
      (node (ref "E4") (pin "3") (pinfunction "A_3") (pintype "input"))
      (node (ref "E4") (pin "4") (pinfunction "B_4") (pintype "input"))
      (node (ref "E4") (pin "5") (pinfunction "C_5") (pintype "input"))
      (node (ref "E4") (pin "6") (pinfunction "D_6") (pintype "input"))
      (node (ref "E42") (pin "5") (pinfunction "I1_5") (pintype "input"))
      (node (ref "E42") (pin "6") (pinfunction "I0_6") (pintype "input"))
      (node (ref "E43") (pin "9") (pinfunction "A_9") (pintype "input"))
      (node (ref "E46") (pin "9") (pinfunction "SER_9") (pintype "input"))
      (node (ref "E47") (pin "2") (pinfunction "A<B_I_2") (pintype "input"))
      (node (ref "E47") (pin "4") (pinfunction "A>B_I_4") (pintype "input"))
      (node (ref "E5") (pin "3") (pinfunction "A_3") (pintype "input"))
      (node (ref "E5") (pin "4") (pinfunction "B_4") (pintype "input"))
      (node (ref "E5") (pin "5") (pinfunction "C_5") (pintype "input"))
      (node (ref "E53") (pin "10") (pinfunction "I1_10") (pintype "input"))
      (node (ref "E53") (pin "5") (pinfunction "I1_5") (pintype "input"))
      (node (ref "E53") (pin "7") (pinfunction "I1_7") (pintype "input"))
      (node (ref "E6") (pin "3") (pinfunction "A_3") (pintype "input"))
      (node (ref "E6") (pin "4") (pinfunction "B_4") (pintype "input"))
      (node (ref "E6") (pin "5") (pinfunction "C_5") (pintype "input"))
      (node (ref "E6") (pin "6") (pinfunction "D_6") (pintype "input"))
      (node (ref "J1") (pin "A") (pinfunction "P_A") (pintype "passive"))
      (node (ref "J1") (pin "AA") (pinfunction "P_AA") (pintype "passive"))
      (node (ref "J1") (pin "B") (pinfunction "P_B") (pintype "passive"))
      (node (ref "J1") (pin "C") (pinfunction "P_C") (pintype "passive"))
      (node (ref "J1") (pin "CC") (pinfunction "P_CC") (pintype "passive"))
      (node (ref "J1") (pin "E") (pinfunction "P_E") (pintype "passive"))
      (node (ref "J1") (pin "EE") (pinfunction "P_EE") (pintype "passive"))
      (node (ref "J1") (pin "H") (pinfunction "P_H") (pintype "passive"))
      (node (ref "J1") (pin "HH") (pinfunction "P_HH") (pintype "passive"))
      (node (ref "J1") (pin "K") (pinfunction "P_K") (pintype "passive"))
      (node (ref "J1") (pin "KK") (pinfunction "P_KK") (pintype "passive"))
      (node (ref "J1") (pin "M") (pinfunction "P_M") (pintype "passive"))
      (node (ref "J1") (pin "MM") (pinfunction "P_MM") (pintype "passive"))
      (node (ref "J1") (pin "P") (pinfunction "P_P") (pintype "passive"))
      (node (ref "J1") (pin "PP") (pinfunction "P_PP") (pintype "passive"))
      (node (ref "J1") (pin "S") (pinfunction "P_S") (pintype "passive"))
      (node (ref "J1") (pin "SS") (pinfunction "P_SS") (pintype "passive"))
      (node (ref "J1") (pin "U") (pinfunction "P_U") (pintype "passive"))
      (node (ref "J1") (pin "UU") (pinfunction "P_UU") (pintype "passive"))
      (node (ref "J1") (pin "W") (pinfunction "P_W") (pintype "passive"))
      (node (ref "J1") (pin "Y") (pinfunction "P_Y") (pintype "passive"))
      (node (ref "J2") (pin "B") (pinfunction "P_B") (pintype "passive"))
      (node (ref "J2") (pin "BB") (pinfunction "P_BB") (pintype "passive"))
      (node (ref "J2") (pin "D") (pinfunction "P_D") (pintype "passive"))
      (node (ref "J2") (pin "DD") (pinfunction "P_DD") (pintype "passive"))
      (node (ref "J2") (pin "F") (pinfunction "P_F") (pintype "passive"))
      (node (ref "J2") (pin "FF") (pinfunction "P_FF") (pintype "passive"))
      (node (ref "J2") (pin "J") (pinfunction "P_J") (pintype "passive"))
      (node (ref "J2") (pin "JJ") (pinfunction "P_JJ") (pintype "passive"))
      (node (ref "J2") (pin "L") (pinfunction "P_L") (pintype "passive"))
      (node (ref "J2") (pin "LL") (pinfunction "P_LL") (pintype "passive"))
      (node (ref "J2") (pin "N") (pinfunction "P_N") (pintype "passive"))
      (node (ref "J2") (pin "NN") (pinfunction "P_NN") (pintype "passive"))
      (node (ref "J2") (pin "R") (pinfunction "P_R") (pintype "passive"))
      (node (ref "J2") (pin "RR") (pinfunction "P_RR") (pintype "passive"))
      (node (ref "J2") (pin "T") (pinfunction "P_T") (pintype "passive"))
      (node (ref "J2") (pin "TT") (pinfunction "P_TT") (pintype "passive"))
      (node (ref "J2") (pin "V") (pinfunction "P_V") (pintype "passive"))
      (node (ref "J2") (pin "VV") (pinfunction "P_VV") (pintype "passive"))
      (node (ref "J2") (pin "X") (pinfunction "P_X") (pintype "passive"))
      (node (ref "J2") (pin "Z") (pinfunction "P_Z") (pintype "passive"))
      (node (ref "OMNIBUS") (pin "AC2") (pinfunction "1_AC2") (pintype "bidirectional"))
      (node (ref "OMNIBUS") (pin "AF1") (pinfunction "1_AF1") (pintype "bidirectional"))
      (node (ref "OMNIBUS") (pin "AF2") (pinfunction "1_AF2") (pintype "bidirectional"))
      (node (ref "OMNIBUS") (pin "AN1") (pinfunction "1_AN1") (pintype "bidirectional"))
      (node (ref "OMNIBUS") (pin "AN2") (pinfunction "1_AN2") (pintype "bidirectional"))
      (node (ref "OMNIBUS") (pin "AT1") (pinfunction "1_AT1") (pintype "bidirectional"))
      (node (ref "OMNIBUS") (pin "AT2") (pinfunction "1_AT2") (pintype "bidirectional"))
      (node (ref "OMNIBUS") (pin "BC1") (pinfunction "1_BC1") (pintype "bidirectional"))
      (node (ref "OMNIBUS") (pin "BC2") (pinfunction "1_BC2") (pintype "bidirectional"))
      (node (ref "OMNIBUS") (pin "BF1") (pinfunction "1_BF1") (pintype "bidirectional"))
      (node (ref "OMNIBUS") (pin "BF2") (pinfunction "1_BF2") (pintype "bidirectional"))
      (node (ref "OMNIBUS") (pin "BN1") (pinfunction "1_BN1") (pintype "bidirectional"))
      (node (ref "OMNIBUS") (pin "BN2") (pinfunction "1_BN2") (pintype "bidirectional"))
      (node (ref "OMNIBUS") (pin "BT1") (pinfunction "1_BT1") (pintype "bidirectional"))
      (node (ref "OMNIBUS") (pin "BT2") (pinfunction "1_BT2") (pintype "bidirectional"))
      (node (ref "OMNIBUS") (pin "CC1") (pinfunction "1_CC1") (pintype "bidirectional"))
      (node (ref "OMNIBUS") (pin "CC2") (pinfunction "1_CC2") (pintype "bidirectional"))
      (node (ref "OMNIBUS") (pin "CF1") (pinfunction "1_CF1") (pintype "bidirectional"))
      (node (ref "OMNIBUS") (pin "CF2") (pinfunction "1_CF2") (pintype "bidirectional"))
      (node (ref "OMNIBUS") (pin "CN1") (pinfunction "1_CN1") (pintype "bidirectional"))
      (node (ref "OMNIBUS") (pin "CN2") (pinfunction "1_CN2") (pintype "bidirectional"))
      (node (ref "OMNIBUS") (pin "CT1") (pinfunction "1_CT1") (pintype "bidirectional"))
      (node (ref "OMNIBUS") (pin "CT2") (pinfunction "1_CT2") (pintype "bidirectional"))
      (node (ref "OMNIBUS") (pin "DC1") (pinfunction "1_DC1") (pintype "bidirectional"))
      (node (ref "OMNIBUS") (pin "DC2") (pinfunction "1_DC2") (pintype "bidirectional"))
      (node (ref "OMNIBUS") (pin "DF1") (pinfunction "1_DF1") (pintype "bidirectional"))
      (node (ref "OMNIBUS") (pin "DF2") (pinfunction "1_DF2") (pintype "bidirectional"))
      (node (ref "OMNIBUS") (pin "DN1") (pinfunction "1_DN1") (pintype "bidirectional"))
      (node (ref "OMNIBUS") (pin "DN2") (pinfunction "1_DN2") (pintype "bidirectional"))
      (node (ref "OMNIBUS") (pin "DT1") (pinfunction "1_DT1") (pintype "bidirectional"))
      (node (ref "OMNIBUS") (pin "DT2") (pinfunction "1_DT2") (pintype "bidirectional"))
      (node (ref "R11") (pin "1") (pinfunction "1_1") (pintype "passive"))
      (node (ref "R16") (pin "1") (pinfunction "1_1") (pintype "passive"))
      (node (ref "R20") (pin "1") (pinfunction "1_1") (pintype "passive"))
      (node (ref "R23") (pin "1") (pinfunction "1_1") (pintype "passive"))
      (node (ref "R25") (pin "1") (pinfunction "1_1") (pintype "passive"))
      (node (ref "R27") (pin "1") (pinfunction "1_1") (pintype "passive"))
      (node (ref "R30") (pin "1") (pinfunction "1_1") (pintype "passive"))
      (node (ref "R31") (pin "1") (pinfunction "1_1") (pintype "passive"))
      (node (ref "R34") (pin "1") (pinfunction "1_1") (pintype "passive"))
      (node (ref "R35") (pin "1") (pinfunction "1_1") (pintype "passive"))
      (node (ref "R37") (pin "1") (pinfunction "1_1") (pintype "passive"))
      (node (ref "R39") (pin "1") (pinfunction "1_1") (pintype "passive"))
      (node (ref "R41") (pin "1") (pinfunction "1_1") (pintype "passive"))
      (node (ref "R44") (pin "1") (pinfunction "1_1") (pintype "passive"))
      (node (ref "R45") (pin "1") (pinfunction "1_1") (pintype "passive"))
      (node (ref "R47") (pin "1") (pinfunction "1_1") (pintype "passive"))
      (node (ref "R49") (pin "1") (pinfunction "1_1") (pintype "passive"))
      (node (ref "R51") (pin "1") (pinfunction "1_1") (pintype "passive"))
      (node (ref "R53") (pin "1") (pinfunction "1_1") (pintype "passive"))
    )
    (net (code "42") (name "GO") (class "Default")
      (node (ref "E19") (pin "11") (pinfunction "CLK_11") (pintype "input"))
      (node (ref "E45") (pin "11") (pinfunction "O_11") (pintype "output"))
      (node (ref "E9") (pin "1") (pinfunction "I_1") (pintype "input"))
    )
    (net (code "43") (name "HALF_BLOCK") (class "Default")
      (node (ref "E") (pin "S2") (pinfunction "P_S2") (pintype "passive"))
      (node (ref "E14") (pin "4") (pinfunction "I0_4") (pintype "input"))
      (node (ref "E5") (pin "6") (pinfunction "D_6") (pintype "input"))
    )
    (net (code "44") (name "HEADER_A") (class "Default")
      (node (ref "E19") (pin "6") (pinfunction "~{Q}_6") (pintype "output"))
      (node (ref "E20") (pin "2") (pinfunction "D_2") (pintype "input"))
    )
    (net (code "45") (name "HEADER_B") (class "Default")
      (node (ref "E20") (pin "12") (pinfunction "D_12") (pintype "input"))
      (node (ref "E20") (pin "5") (pinfunction "Q_5") (pintype "output"))
      (node (ref "E26") (pin "3") (pinfunction "I1_3") (pintype "input"))
      (node (ref "E30") (pin "6") (pinfunction "I1_6") (pintype "input"))
    )
    (net (code "46") (name "HEADER_C") (class "Default")
      (node (ref "E20") (pin "9") (pinfunction "Q_9") (pintype "output"))
      (node (ref "E26") (pin "6") (pinfunction "I1_6") (pintype "input"))
      (node (ref "E27") (pin "4") (pinfunction "I0_4") (pintype "input"))
      (node (ref "E28") (pin "10") (pinfunction "I10_10") (pintype "input"))
    )
    (net (code "47") (name "HEADER_D") (class "Default")
      (node (ref "E22") (pin "12") (pinfunction "D_12") (pintype "input"))
      (node (ref "E24") (pin "9") (pinfunction "Q_9") (pintype "output"))
      (node (ref "E29") (pin "3") (pinfunction "I1_3") (pintype "input"))
      (node (ref "E37") (pin "1") (pinfunction "CLR_1") (pintype "input"))
      (node (ref "E41") (pin "11") (pinfunction "CLK_11") (pintype "input"))
    )
    (net (code "48") (name "HEADER_E") (class "Default")
      (node (ref "E13") (pin "2") (pinfunction "I0_2") (pintype "input"))
      (node (ref "E22") (pin "2") (pinfunction "D_2") (pintype "input"))
      (node (ref "E22") (pin "9") (pinfunction "Q_9") (pintype "output"))
      (node (ref "E40") (pin "6") (pinfunction "I1_6") (pintype "input"))
    )
    (net (code "49") (name "IDLE") (class "Default")
      (node (ref "E") (pin "C1") (pinfunction "P_C1") (pintype "passive"))
      (node (ref "E18") (pin "6") (pinfunction "~{Q}_6") (pintype "output"))
      (node (ref "E26") (pin "2") (pinfunction "I0_2") (pintype "input"))
      (node (ref "E29") (pin "2") (pinfunction "I0_2") (pintype "input"))
      (node (ref "E29") (pin "8") (pinfunction "I0_8") (pintype "input"))
    )
    (net (code "50") (name "INC_CNTRS") (class "Default")
      (node (ref "E10") (pin "12") (pinfunction "O_12") (pintype "output"))
      (node (ref "E11") (pin "1") (pinfunction "I_1") (pintype "input"))
      (node (ref "E12") (pin "12") (pinfunction "I0_12") (pintype "input"))
      (node (ref "E12") (pin "4") (pinfunction "I0_4") (pintype "input"))
    )
    (net (code "51") (name "INH_12TH_BIT") (class "Default")
      (node (ref "E13") (pin "12") (pinfunction "I1_12") (pintype "input"))
      (node (ref "E15") (pin "8") (pinfunction "~{Q}_8") (pintype "output"))
    )
    (net (code "52") (name "LAST_BRK") (class "Default")
      (node (ref "E39") (pin "4") (pinfunction "I1_4") (pintype "input"))
      (node (ref "F") (pin "N2") (pinfunction "P_N2") (pintype "passive"))
    )
    (net (code "53") (name "LAST_WORD") (class "Default")
      (node (ref "C40") (pin "1") (pinfunction "1_1") (pintype "passive"))
      (node (ref "E12") (pin "9") (pinfunction "I0_9") (pintype "input"))
      (node (ref "R55") (pin "2") (pinfunction "2_2") (pintype "passive"))
    )
    (net (code "54") (name "LAST_WORD_PL") (class "Default")
      (node (ref "E11") (pin "8") (pinfunction "O_8") (pintype "output"))
      (node (ref "F") (pin "E1") (pinfunction "P_E1") (pintype "passive"))
    )
    (net (code "55") (name "LD_DISK_ADDRS") (class "Default")
      (node (ref "E") (pin "M2") (pinfunction "P_M2") (pintype "passive"))
      (node (ref "E32") (pin "6") (pinfunction "O_6") (pintype "output"))
      (node (ref "E39") (pin "1") (pinfunction "I0_1") (pintype "input"))
      (node (ref "E46") (pin "8") (pinfunction "PE_8") (pintype "input"))
    )
    (net (code "56") (name "NOT_CHK_HEADER_CMD") (class "Default")
      (node (ref "E24") (pin "2") (pinfunction "D_2") (pintype "input"))
      (node (ref "E34") (pin "8") (pinfunction "O_8") (pintype "output"))
    )
    (net (code "57") (name "Net-(C26-Pad1)") (class "Default")
      (node (ref "C26") (pin "1") (pinfunction "1_1") (pintype "passive"))
      (node (ref "D3") (pin "A") (pinfunction "A_A") (pintype "passive"))
      (node (ref "R19") (pin "1") (pinfunction "1_1") (pintype "passive"))
    )
    (net (code "58") (name "Net-(C38-Pad2)") (class "Default")
      (node (ref "C38") (pin "2") (pinfunction "2_2") (pintype "passive"))
      (node (ref "CR1") (pin "1") (pinfunction "1_1") (pintype "passive"))
      (node (ref "R16") (pin "2") (pinfunction "2_2") (pintype "passive"))
    )
    (net (code "59") (name "Net-(CR1-Pad2)") (class "Default")
      (node (ref "CR1") (pin "2") (pinfunction "2_2") (pintype "passive"))
      (node (ref "R14") (pin "1") (pinfunction "1_1") (pintype "passive"))
    )
    (net (code "60") (name "Net-(E3A-RCO)") (class "Default")
      (node (ref "E3") (pin "15") (pinfunction "RCO_15") (pintype "output"))
      (node (ref "E4") (pin "10") (pinfunction "ENT_10") (pintype "input"))
      (node (ref "E4") (pin "7") (pinfunction "ENP_7") (pintype "input"))
    )
    (net (code "61") (name "Net-(E4A-RCO)") (class "Default")
      (node (ref "E4") (pin "15") (pinfunction "RCO_15") (pintype "output"))
      (node (ref "R55") (pin "1") (pinfunction "1_1") (pintype "passive"))
    )
    (net (code "62") (name "Net-(E5A-ENP)") (class "Default")
      (node (ref "E5") (pin "7") (pinfunction "ENP_7") (pintype "input"))
      (node (ref "E6") (pin "15") (pinfunction "RCO_15") (pintype "output"))
    )
    (net (code "63") (name "Net-(E7B-I)") (class "Default")
      (node (ref "E7") (pin "3") (pinfunction "I_3") (pintype "input"))
      (node (ref "E8") (pin "3") (pinfunction "O_3") (pintype "output"))
      (node (ref "E8") (pin "4") (pinfunction "I0_4") (pintype "input"))
    )
    (net (code "64") (name "Net-(E7E-O)") (class "Default")
      (node (ref "E7") (pin "10") (pinfunction "O_10") (pintype "output"))
      (node (ref "R7") (pin "1") (pinfunction "1_1") (pintype "passive"))
    )
    (net (code "65") (name "Net-(E7F-O)") (class "Default")
      (node (ref "E7") (pin "12") (pinfunction "O_12") (pintype "output"))
      (node (ref "R6") (pin "1") (pinfunction "1_1") (pintype "passive"))
    )
    (net (code "66") (name "Net-(E8D-I0)") (class "Default")
      (node (ref "C34") (pin "1") (pinfunction "1_1") (pintype "passive"))
      (node (ref "E8") (pin "12") (pinfunction "I0_12") (pintype "input"))
      (node (ref "R6") (pin "2") (pinfunction "2_2") (pintype "passive"))
    )
    (net (code "67") (name "Net-(E10B-I0)") (class "Default")
      (node (ref "E10") (pin "3") (pinfunction "I0_3") (pintype "input"))
      (node (ref "E12") (pin "3") (pinfunction "O_3") (pintype "output"))
    )
    (net (code "68") (name "Net-(E10C-I0)") (class "Default")
      (node (ref "E10") (pin "9") (pinfunction "I0_9") (pintype "input"))
      (node (ref "E2") (pin "14") (pinfunction "QA_14") (pintype "output"))
    )
    (net (code "69") (name "Net-(E10C-I1)") (class "Default")
      (node (ref "E10") (pin "10") (pinfunction "I1_10") (pintype "input"))
      (node (ref "E2") (pin "13") (pinfunction "QB_13") (pintype "output"))
    )
    (net (code "70") (name "Net-(E10C-I2)") (class "Default")
      (node (ref "E10") (pin "11") (pinfunction "I2_11") (pintype "input"))
      (node (ref "E2") (pin "11") (pinfunction "QD_11") (pintype "output"))
    )
    (net (code "71") (name "Net-(E11F-I)") (class "Default")
      (node (ref "E11") (pin "13") (pinfunction "I_13") (pintype "input"))
      (node (ref "E12") (pin "1") (pinfunction "I0_1") (pintype "input"))
      (node (ref "E9") (pin "12") (pinfunction "O_12") (pintype "output"))
    )
    (net (code "72") (name "Net-(E11F-O)") (class "Default")
      (node (ref "E11") (pin "12") (pinfunction "O_12") (pintype "output"))
      (node (ref "R3") (pin "1") (pinfunction "1_1") (pintype "passive"))
    )
    (net (code "73") (name "Net-(E12A-I1)") (class "Default")
      (node (ref "C32") (pin "1") (pinfunction "1_1") (pintype "passive"))
      (node (ref "E12") (pin "2") (pinfunction "I1_2") (pintype "input"))
      (node (ref "R3") (pin "2") (pinfunction "2_2") (pintype "passive"))
    )
    (net (code "74") (name "Net-(E12B-O)") (class "Default")
      (node (ref "E12") (pin "6") (pinfunction "O_6") (pintype "output"))
      (node (ref "E13") (pin "11") (pinfunction "I0_11") (pintype "input"))
    )
    (net (code "75") (name "Net-(E13A-O)") (class "Default")
      (node (ref "E13") (pin "1") (pinfunction "O_1") (pintype "output"))
      (node (ref "E9") (pin "13") (pinfunction "I_13") (pintype "input"))
    )
    (net (code "76") (name "Net-(E13B-I0)") (class "Default")
      (node (ref "E13") (pin "10") (pinfunction "O_10") (pintype "output"))
      (node (ref "E13") (pin "5") (pinfunction "I0_5") (pintype "input"))
    )
    (net (code "77") (name "Net-(E14B-O)") (class "Default")
      (node (ref "E14") (pin "6") (pinfunction "O_6") (pintype "output"))
      (node (ref "E15") (pin "12") (pinfunction "D_12") (pintype "input"))
    )
    (net (code "78") (name "Net-(E14D-I1)") (class "Default")
      (node (ref "E14") (pin "13") (pinfunction "I1_13") (pintype "input"))
      (node (ref "E29") (pin "4") (pinfunction "O_4") (pintype "output"))
    )
    (net (code "79") (name "Net-(E15B-CLK)") (class "Default")
      (node (ref "C30") (pin "1") (pinfunction "1_1") (pintype "passive"))
      (node (ref "E15") (pin "11") (pinfunction "CLK_11") (pintype "input"))
      (node (ref "R1") (pin "2") (pinfunction "2_2") (pintype "passive"))
    )
    (net (code "80") (name "Net-(E16B-I0)") (class "Default")
      (node (ref "E16") (pin "4") (pinfunction "I0_4") (pintype "input"))
      (node (ref "E30") (pin "1") (pinfunction "O_1") (pintype "output"))
    )
    (net (code "81") (name "Net-(E16B-O)") (class "Default")
      (node (ref "E16") (pin "6") (pinfunction "O_6") (pintype "output"))
      (node (ref "E37") (pin "10") (pinfunction "PRE_10") (pintype "input"))
    )
    (net (code "82") (name "Net-(E16C-I0)") (class "Default")
      (node (ref "E16") (pin "9") (pinfunction "I0_9") (pintype "input"))
      (node (ref "E34") (pin "4") (pinfunction "I1_4") (pintype "input"))
      (node (ref "E36") (pin "1") (pinfunction "I_1") (pintype "input"))
      (node (ref "E39") (pin "10") (pinfunction "I1_10") (pintype "input"))
      (node (ref "E45") (pin "8") (pinfunction "O_8") (pintype "output"))
    )
    (net (code "83") (name "Net-(E16C-I1)") (class "Default")
      (node (ref "E16") (pin "10") (pinfunction "I1_10") (pintype "input"))
      (node (ref "E34") (pin "3") (pinfunction "I0_3") (pintype "input"))
      (node (ref "E41") (pin "2") (pinfunction "D_2") (pintype "input"))
      (node (ref "E41") (pin "5") (pinfunction "Q_5") (pintype "output"))
    )
    (net (code "84") (name "Net-(E16D-I1)") (class "Default")
      (node (ref "C35") (pin "1") (pinfunction "1_1") (pintype "passive"))
      (node (ref "E16") (pin "13") (pinfunction "I1_13") (pintype "input"))
      (node (ref "R7") (pin "2") (pinfunction "2_2") (pintype "passive"))
    )
    (net (code "85") (name "Net-(E17A-O)") (class "Default")
      (node (ref "E17") (pin "3") (pinfunction "O_3") (pintype "output"))
      (node (ref "E17") (pin "4") (pinfunction "I0_4") (pintype "input"))
      (node (ref "E17") (pin "5") (pinfunction "I1_5") (pintype "input"))
    )
    (net (code "86") (name "Net-(E17B-O)") (class "Default")
      (node (ref "E17") (pin "13") (pinfunction "I1_13") (pintype "input"))
      (node (ref "E17") (pin "6") (pinfunction "O_6") (pintype "output"))
    )
    (net (code "87") (name "Net-(E17C-I1)") (class "Default")
      (node (ref "E17") (pin "10") (pinfunction "I1_10") (pintype "input"))
      (node (ref "E17") (pin "11") (pinfunction "O_11") (pintype "output"))
    )
    (net (code "88") (name "Net-(E18A-CLK)") (class "Default")
      (node (ref "E18") (pin "3") (pinfunction "CLK_3") (pintype "input"))
      (node (ref "E9") (pin "4") (pinfunction "O_4") (pintype "output"))
    )
    (net (code "89") (name "Net-(E18A-CLR)") (class "Default")
      (node (ref "E18") (pin "1") (pinfunction "CLR_1") (pintype "input"))
      (node (ref "E26") (pin "13") (pinfunction "O_13") (pintype "output"))
      (node (ref "E9") (pin "5") (pinfunction "I_5") (pintype "input"))
    )
    (net (code "90") (name "Net-(E19A-PRE)") (class "Default")
      (node (ref "E19") (pin "4") (pinfunction "PRE_4") (pintype "input"))
      (node (ref "E26") (pin "1") (pinfunction "O_1") (pintype "output"))
    )
    (net (code "91") (name "Net-(E20A-CLR)") (class "Default")
      (node (ref "E20") (pin "1") (pinfunction "CLR_1") (pintype "input"))
      (node (ref "E26") (pin "4") (pinfunction "O_4") (pintype "output"))
    )
    (net (code "92") (name "Net-(E20B-CLR)") (class "Default")
      (node (ref "E20") (pin "13") (pinfunction "CLR_13") (pintype "input"))
      (node (ref "E29") (pin "10") (pinfunction "O_10") (pintype "output"))
    )
    (net (code "93") (name "Net-(E21A-CLR)") (class "Default")
      (node (ref "E21") (pin "1") (pinfunction "CLR_1") (pintype "input"))
      (node (ref "E23") (pin "1") (pinfunction "O_1") (pintype "output"))
    )
    (net (code "94") (name "Net-(E22A-CLR)") (class "Default")
      (node (ref "E22") (pin "1") (pinfunction "CLR_1") (pintype "input"))
      (node (ref "E23") (pin "10") (pinfunction "O_10") (pintype "output"))
    )
    (net (code "95") (name "Net-(E22B-CLK)") (class "Default")
      (node (ref "E22") (pin "11") (pinfunction "CLK_11") (pintype "input"))
      (node (ref "E32") (pin "3") (pinfunction "O_3") (pintype "output"))
    )
    (net (code "96") (name "Net-(E22B-CLR)") (class "Default")
      (node (ref "E22") (pin "13") (pinfunction "CLR_13") (pintype "input"))
      (node (ref "E23") (pin "13") (pinfunction "O_13") (pintype "output"))
    )
    (net (code "97") (name "Net-(E24A-CLR)") (class "Default")
      (node (ref "E24") (pin "1") (pinfunction "CLR_1") (pintype "input"))
      (node (ref "E29") (pin "1") (pinfunction "O_1") (pintype "output"))
    )
    (net (code "98") (name "Net-(E24B-CLR)") (class "Default")
      (node (ref "E24") (pin "13") (pinfunction "CLR_13") (pintype "input"))
      (node (ref "E40") (pin "4") (pinfunction "O_4") (pintype "output"))
    )
    (net (code "99") (name "Net-(E25A-I0)") (class "Default")
      (node (ref "E25") (pin "1") (pinfunction "I0_1") (pintype "input"))
      (node (ref "E25") (pin "8") (pinfunction "O_8") (pintype "output"))
    )
    (net (code "100") (name "Net-(E25A-O)") (class "Default")
      (node (ref "E25") (pin "3") (pinfunction "O_3") (pintype "output"))
      (node (ref "E9") (pin "3") (pinfunction "I_3") (pintype "input"))
    )
    (net (code "101") (name "Net-(E25B-O)") (class "Default")
      (node (ref "E25") (pin "6") (pinfunction "O_6") (pintype "output"))
      (node (ref "E26") (pin "11") (pinfunction "I0_11") (pintype "input"))
    )
    (net (code "102") (name "Net-(E26D-I1)") (class "Default")
      (node (ref "E26") (pin "12") (pinfunction "I1_12") (pintype "input"))
      (node (ref "E27") (pin "3") (pinfunction "O_3") (pintype "output"))
    )
    (net (code "103") (name "Net-(E27A-I0)") (class "Default")
      (node (ref "E27") (pin "1") (pinfunction "I0_1") (pintype "input"))
      (node (ref "E39") (pin "6") (pinfunction "O_6") (pintype "output"))
    )
    (net (code "104") (name "Net-(E29D-I0)") (class "Default")
      (node (ref "C39") (pin "1") (pinfunction "1_1") (pintype "passive"))
      (node (ref "E29") (pin "11") (pinfunction "I0_11") (pintype "input"))
      (node (ref "R18") (pin "2") (pinfunction "2_2") (pintype "passive"))
    )
    (net (code "105") (name "Net-(E30B-I0)") (class "Default")
      (node (ref "E30") (pin "13") (pinfunction "O_13") (pintype "output"))
      (node (ref "E30") (pin "5") (pinfunction "I0_5") (pintype "input"))
    )
    (net (code "106") (name "Net-(E30B-O)") (class "Default")
      (node (ref "E30") (pin "4") (pinfunction "O_4") (pintype "output"))
      (node (ref "E37") (pin "12") (pinfunction "D_12") (pintype "input"))
    )
    (net (code "107") (name "Net-(E32B-I1)") (class "Default")
      (node (ref "E32") (pin "11") (pinfunction "O_11") (pintype "output"))
      (node (ref "E32") (pin "5") (pinfunction "I1_5") (pintype "input"))
    )
    (net (code "108") (name "Net-(E33A-I1)") (class "Default")
      (node (ref "E33") (pin "2") (pinfunction "I1_2") (pintype "input"))
      (node (ref "E33") (pin "6") (pinfunction "O_6") (pintype "output"))
      (node (ref "E40") (pin "8") (pinfunction "I0_8") (pintype "input"))
    )
    (net (code "109") (name "Net-(E33A-O)") (class "Default")
      (node (ref "E33") (pin "3") (pinfunction "O_3") (pintype "output"))
      (node (ref "E34") (pin "2") (pinfunction "I1_2") (pintype "input"))
    )
    (net (code "110") (name "Net-(E33C-O)") (class "Default")
      (node (ref "E33") (pin "8") (pinfunction "O_8") (pintype "output"))
      (node (ref "E34") (pin "1") (pinfunction "I0_1") (pintype "input"))
    )
    (net (code "111") (name "Net-(E34A-O)") (class "Default")
      (node (ref "E34") (pin "12") (pinfunction "O_12") (pintype "output"))
      (node (ref "E34") (pin "5") (pinfunction "I2_5") (pintype "input"))
    )
    (net (code "112") (name "Net-(E36A-O)") (class "Default")
      (node (ref "E36") (pin "2") (pinfunction "O_2") (pintype "output"))
      (node (ref "E41") (pin "3") (pinfunction "CLK_3") (pintype "input"))
    )
    (net (code "113") (name "Net-(E36E-O)") (class "Default")
      (node (ref "E36") (pin "10") (pinfunction "O_10") (pintype "output"))
      (node (ref "R18") (pin "1") (pinfunction "1_1") (pintype "passive"))
    )
    (net (code "114") (name "Net-(E38A-C)") (class "Default")
      (node (ref "C33") (pin "1") (pinfunction "1_1") (pintype "passive"))
      (node (ref "E38") (pin "14") (pinfunction "C_14") (pintype "input"))
    )
    (net (code "115") (name "Net-(E38A-R{slash}C)") (class "Default")
      (node (ref "C33") (pin "2") (pinfunction "2_2") (pintype "passive"))
      (node (ref "E38") (pin "15") (pinfunction "R/C_15") (pintype "input"))
      (node (ref "R5") (pin "1") (pinfunction "1_1") (pintype "passive"))
    )
    (net (code "116") (name "Net-(E38B-C)") (class "Default")
      (node (ref "C36") (pin "1") (pinfunction "1_1") (pintype "passive"))
      (node (ref "E38") (pin "6") (pinfunction "C_6") (pintype "input"))
    )
    (net (code "117") (name "Net-(E38B-R{slash}C)") (class "Default")
      (node (ref "C36") (pin "2") (pinfunction "2_2") (pintype "passive"))
      (node (ref "E38") (pin "7") (pinfunction "R/C_7") (pintype "input"))
      (node (ref "R13") (pin "1") (pinfunction "1_1") (pintype "passive"))
    )
    (net (code "118") (name "Net-(E39A-O)") (class "Default")
      (node (ref "E39") (pin "12") (pinfunction "O_12") (pintype "output"))
      (node (ref "E45") (pin "12") (pinfunction "I0_12") (pintype "input"))
    )
    (net (code "119") (name "Net-(E39C-I2)") (class "Default")
      (node (ref "E39") (pin "11") (pinfunction "I2_11") (pintype "input"))
      (node (ref "E41") (pin "6") (pinfunction "~{Q}_6") (pintype "output"))
    )
    (net (code "120") (name "Net-(E40A-I0)") (class "Default")
      (node (ref "E40") (pin "10") (pinfunction "O_10") (pintype "output"))
      (node (ref "E40") (pin "2") (pinfunction "I0_2") (pintype "input"))
    )
    (net (code "121") (name "Net-(E43A-C)") (class "Default")
      (node (ref "C26") (pin "2") (pinfunction "2_2") (pintype "passive"))
      (node (ref "E43") (pin "14") (pinfunction "C_14") (pintype "input"))
    )
    (net (code "122") (name "Net-(E43A-R{slash}C)") (class "Default")
      (node (ref "D3") (pin "C") (pinfunction "C_C") (pintype "passive"))
      (node (ref "E43") (pin "15") (pinfunction "R/C_15") (pintype "input"))
    )
    (net (code "123") (name "Net-(E43B-C)") (class "Default")
      (node (ref "C31") (pin "1") (pinfunction "1_1") (pintype "passive"))
      (node (ref "E43") (pin "6") (pinfunction "C_6") (pintype "input"))
    )
    (net (code "124") (name "Net-(E43B-R{slash}C)") (class "Default")
      (node (ref "C31") (pin "2") (pinfunction "2_2") (pintype "passive"))
      (node (ref "E43") (pin "7") (pinfunction "R/C_7") (pintype "input"))
      (node (ref "R2") (pin "2") (pinfunction "2_2") (pintype "passive"))
    )
    (net (code "125") (name "Net-(E45A-I0)") (class "Default")
      (node (ref "E45") (pin "1") (pinfunction "I0_1") (pintype "input"))
      (node (ref "E51") (pin "3") (pinfunction "O_3") (pintype "output"))
    )
    (net (code "126") (name "Net-(E45A-O)") (class "Default")
      (node (ref "E45") (pin "3") (pinfunction "O_3") (pintype "output"))
      (node (ref "E45") (pin "4") (pinfunction "I0_4") (pintype "input"))
    )
    (net (code "127") (name "Net-(E45B-O)") (class "Default")
      (node (ref "E45") (pin "6") (pinfunction "O_6") (pintype "output"))
      (node (ref "E45") (pin "9") (pinfunction "I0_9") (pintype "input"))
    )
    (net (code "128") (name "Net-(E47A-A0)") (class "Default")
      (node (ref "E47") (pin "10") (pinfunction "A0_10") (pintype "input"))
      (node (ref "E53") (pin "14") (pinfunction "O_14") (pintype "output"))
    )
    (net (code "129") (name "Net-(E47A-A2)") (class "Default")
      (node (ref "E47") (pin "13") (pinfunction "A2_13") (pintype "input"))
      (node (ref "E53") (pin "3") (pinfunction "O_3") (pintype "output"))
    )
    (net (code "130") (name "Net-(E47A-A3)") (class "Default")
      (node (ref "E47") (pin "15") (pinfunction "A3_15") (pintype "input"))
      (node (ref "E53") (pin "2") (pinfunction "O_2") (pintype "output"))
    )
    (net (code "131") (name "Net-(E51A-I0)") (class "Default")
      (node (ref "C37") (pin "1") (pinfunction "1_1") (pintype "passive"))
      (node (ref "E51") (pin "13") (pinfunction "O_13") (pintype "output"))
      (node (ref "E51") (pin "4") (pinfunction "I0_4") (pintype "input"))
      (node (ref "E51") (pin "5") (pinfunction "I1_5") (pintype "input"))
      (node (ref "R17") (pin "2") (pinfunction "2_2") (pintype "passive"))
    )
    (net (code "132") (name "Net-(E51B-I0)") (class "Default")
      (node (ref "C37") (pin "2") (pinfunction "2_2") (pintype "passive"))
      (node (ref "E51") (pin "6") (pinfunction "I0_6") (pintype "input"))
      (node (ref "E51") (pin "7") (pinfunction "I1_7") (pintype "input"))
      (node (ref "R15") (pin "1") (pinfunction "1_1") (pintype "passive"))
    )
    (net (code "133") (name "Net-(E51B-O)") (class "Default")
      (node (ref "E51") (pin "2") (pinfunction "O_2") (pintype "output"))
      (node (ref "R14") (pin "2") (pinfunction "2_2") (pintype "passive"))
      (node (ref "R15") (pin "2") (pinfunction "2_2") (pintype "passive"))
    )
    (net (code "134") (name "Net-(E51C-O)") (class "Default")
      (node (ref "E51") (pin "14") (pinfunction "O_14") (pintype "output"))
      (node (ref "E54") (pin "7") (pinfunction "I1_7") (pintype "input"))
    )
    (net (code "135") (name "Net-(E51D-I0)") (class "Default")
      (node (ref "C38") (pin "1") (pinfunction "1_1") (pintype "passive"))
      (node (ref "E51") (pin "11") (pinfunction "I0_11") (pintype "input"))
      (node (ref "E51") (pin "12") (pinfunction "I1_12") (pintype "input"))
      (node (ref "R17") (pin "1") (pinfunction "1_1") (pintype "passive"))
    )
    (net (code "136") (name "Net-(J1AF-P)") (class "Default")
      (node (ref "J1") (pin "TT") (pinfunction "P_TT") (pintype "passive"))
      (node (ref "OMNIBUS") (pin "BV2") (pinfunction "1_BV2") (pintype "bidirectional"))
    )
    (net (code "137") (name "Net-(R4-E)") (class "Default")
      (node (ref "R4") (pin "2") (pinfunction "S_2") (pintype "passive"))
      (node (ref "R4") (pin "3") (pinfunction "E_3") (pintype "passive"))
      (node (ref "R5") (pin "2") (pinfunction "2_2") (pintype "passive"))
    )
    (net (code "138") (name "Net-(R12-E)") (class "Default")
      (node (ref "R12") (pin "2") (pinfunction "S_2") (pintype "passive"))
      (node (ref "R12") (pin "3") (pinfunction "E_3") (pintype "passive"))
      (node (ref "R13") (pin "2") (pinfunction "2_2") (pintype "passive"))
    )
    (net (code "139") (name "RDY_S{slash}R{slash}W") (class "Default")
      (node (ref "E") (pin "D1") (pinfunction "P_D1") (pintype "passive"))
      (node (ref "E16") (pin "1") (pinfunction "I0_1") (pintype "input"))
      (node (ref "E39") (pin "2") (pinfunction "I1_2") (pintype "input"))
    )
    (net (code "140") (name "RD_CLK1") (class "Default")
      (node (ref "E") (pin "B1") (pinfunction "P_B1") (pintype "passive"))
      (node (ref "E14") (pin "9") (pinfunction "I0_9") (pintype "input"))
      (node (ref "E7") (pin "8") (pinfunction "O_8") (pintype "output"))
    )
    (net (code "141") (name "RD_CLK2") (class "Default")
      (node (ref "E16") (pin "11") (pinfunction "O_11") (pintype "output"))
      (node (ref "E7") (pin "5") (pinfunction "I_5") (pintype "input"))
      (node (ref "E8") (pin "10") (pinfunction "I1_10") (pintype "input"))
    )
    (net (code "142") (name "RD_SHFT_CRC") (class "Default")
      (node (ref "E30") (pin "10") (pinfunction "O_10") (pintype "output"))
      (node (ref "E40") (pin "11") (pinfunction "I0_11") (pintype "input"))
    )
    (net (code "143") (name "READ") (class "Default")
      (node (ref "E15") (pin "1") (pinfunction "CLR_1") (pintype "input"))
      (node (ref "E37") (pin "8") (pinfunction "~{Q}_8") (pintype "output"))
      (node (ref "E49") (pin "1") (pinfunction "I0_1") (pintype "input"))
      (node (ref "E49") (pin "2") (pinfunction "I1_2") (pintype "input"))
      (node (ref "E8") (pin "1") (pinfunction "I0_1") (pintype "input"))
    )
    (net (code "144") (name "READ_CLK") (class "Default")
      (node (ref "E54") (pin "14") (pinfunction "O_14") (pintype "output"))
      (node (ref "E7") (pin "13") (pinfunction "I_13") (pintype "input"))
      (node (ref "E8") (pin "13") (pinfunction "I1_13") (pintype "input"))
    )
    (net (code "145") (name "READ_DATA_IN") (class "Default")
      (node (ref "E35") (pin "3") (pinfunction "I_3") (pintype "input"))
      (node (ref "E54") (pin "3") (pinfunction "O_3") (pintype "output"))
    )
    (net (code "146") (name "RESTORE") (class "Default")
      (node (ref "E18") (pin "9") (pinfunction "Q_9") (pintype "output"))
      (node (ref "E49") (pin "6") (pinfunction "I0_6") (pintype "input"))
      (node (ref "E49") (pin "7") (pinfunction "I1_7") (pintype "input"))
    )
    (net (code "147") (name "RK_DATA11") (class "Default")
      (node (ref "E28") (pin "4") (pinfunction "I4_4") (pintype "input"))
      (node (ref "E33") (pin "9") (pinfunction "I0_9") (pintype "input"))
      (node (ref "F") (pin "H1") (pinfunction "P_H1") (pintype "passive"))
    )
    (net (code "148") (name "SECTOR_ADDRS1") (class "Default")
      (node (ref "E") (pin "P2") (pinfunction "P_P2") (pintype "passive"))
      (node (ref "E46") (pin "10") (pinfunction "QE_10") (pintype "output"))
      (node (ref "E47") (pin "9") (pinfunction "B0_9") (pintype "input"))
    )
    (net (code "149") (name "SECTOR_ADDRS2") (class "Default")
      (node (ref "E46") (pin "11") (pinfunction "QD_11") (pintype "output"))
      (node (ref "E47") (pin "11") (pinfunction "B1_11") (pintype "input"))
    )
    (net (code "150") (name "SECTOR_ADDRS4") (class "Default")
      (node (ref "E46") (pin "13") (pinfunction "QC_13") (pintype "output"))
      (node (ref "E47") (pin "14") (pinfunction "B2_14") (pintype "input"))
    )
    (net (code "151") (name "SECTOR_ADDRS8") (class "Default")
      (node (ref "E46") (pin "14") (pinfunction "QB_14") (pintype "output"))
      (node (ref "E47") (pin "1") (pinfunction "B3_1") (pintype "input"))
    )
    (net (code "152") (name "SECTOR_EQ") (class "Default")
      (node (ref "E24") (pin "12") (pinfunction "D_12") (pintype "input"))
      (node (ref "E47") (pin "6") (pinfunction "A=B_O_6") (pintype "output"))
    )
    (net (code "153") (name "SECTOR_MK") (class "Default")
      (node (ref "E20") (pin "3") (pinfunction "CLK_3") (pintype "input"))
      (node (ref "E35") (pin "1") (pinfunction "I_1") (pintype "input"))
      (node (ref "E38") (pin "2") (pinfunction "B_2") (pintype "input"))
      (node (ref "E54") (pin "13") (pinfunction "O_13") (pintype "output"))
    )
    (net (code "154") (name "SECTOR_SEEK") (class "Default")
      (node (ref "E24") (pin "5") (pinfunction "Q_5") (pintype "output"))
      (node (ref "E29") (pin "9") (pinfunction "I1_9") (pintype "input"))
      (node (ref "E30") (pin "3") (pinfunction "I1_3") (pintype "input"))
      (node (ref "E47") (pin "3") (pinfunction "A=B_I_3") (pintype "input"))
    )
    (net (code "155") (name "SEEK_ONLY") (class "Default")
      (node (ref "E25") (pin "10") (pinfunction "I1_10") (pintype "input"))
      (node (ref "E25") (pin "11") (pinfunction "O_11") (pintype "output"))
    )
    (net (code "156") (name "SHFT_SURF") (class "Default")
      (node (ref "E46") (pin "1") (pinfunction "CLK_1") (pintype "input"))
      (node (ref "F") (pin "U1") (pinfunction "P_U1") (pintype "passive"))
    )
    (net (code "157") (name "STATE_ENAB_B") (class "Default")
      (node (ref "E13") (pin "3") (pinfunction "I1_3") (pintype "input"))
      (node (ref "E14") (pin "3") (pinfunction "O_3") (pintype "output"))
      (node (ref "E23") (pin "6") (pinfunction "I1_6") (pintype "input"))
      (node (ref "F") (pin "V1") (pinfunction "P_V1") (pintype "passive"))
    )
    (net (code "158") (name "STROBE") (class "Default")
      (node (ref "E") (pin "F2") (pinfunction "P_F2") (pintype "passive"))
      (node (ref "E19") (pin "9") (pinfunction "Q_9") (pintype "output"))
      (node (ref "E25") (pin "9") (pinfunction "I0_9") (pintype "input"))
      (node (ref "E48") (pin "1") (pinfunction "I0_1") (pintype "input"))
      (node (ref "E48") (pin "2") (pinfunction "I1_2") (pintype "input"))
    )
    (net (code "159") (name "TOP_SURF") (class "Default")
      (node (ref "E46") (pin "15") (pinfunction "QA_15") (pintype "output"))
      (node (ref "E48") (pin "6") (pinfunction "I0_6") (pintype "input"))
      (node (ref "E48") (pin "7") (pinfunction "I1_7") (pintype "input"))
    )
    (net (code "160") (name "VCC") (class "Default")
      (node (ref "C1") (pin "1") (pinfunction "1_1") (pintype "passive"))
      (node (ref "C10") (pin "1") (pinfunction "1_1") (pintype "passive"))
      (node (ref "C11") (pin "1") (pinfunction "1_1") (pintype "passive"))
      (node (ref "C12") (pin "1") (pinfunction "1_1") (pintype "passive"))
      (node (ref "C13") (pin "1") (pinfunction "1_1") (pintype "passive"))
      (node (ref "C14") (pin "1") (pinfunction "1_1") (pintype "passive"))
      (node (ref "C15") (pin "1") (pinfunction "1_1") (pintype "passive"))
      (node (ref "C16") (pin "1") (pinfunction "1_1") (pintype "passive"))
      (node (ref "C17") (pin "1") (pinfunction "1_1") (pintype "passive"))
      (node (ref "C18") (pin "1") (pinfunction "1_1") (pintype "passive"))
      (node (ref "C19") (pin "1") (pinfunction "1_1") (pintype "passive"))
      (node (ref "C2") (pin "1") (pinfunction "1_1") (pintype "passive"))
      (node (ref "C20") (pin "1") (pinfunction "1_1") (pintype "passive"))
      (node (ref "C21") (pin "1") (pinfunction "1_1") (pintype "passive"))
      (node (ref "C22") (pin "1") (pinfunction "1_1") (pintype "passive"))
      (node (ref "C23") (pin "1") (pinfunction "1_1") (pintype "passive"))
      (node (ref "C24") (pin "1") (pinfunction "1_1") (pintype "passive"))
      (node (ref "C25") (pin "1") (pinfunction "1_1") (pintype "passive"))
      (node (ref "C27") (pin "+") (pinfunction "+_+") (pintype "passive"))
      (node (ref "C28") (pin "+") (pinfunction "+_+") (pintype "passive"))
      (node (ref "C29") (pin "+") (pinfunction "+_+") (pintype "passive"))
      (node (ref "C3") (pin "1") (pinfunction "1_1") (pintype "passive"))
      (node (ref "C4") (pin "1") (pinfunction "1_1") (pintype "passive"))
      (node (ref "C5") (pin "1") (pinfunction "1_1") (pintype "passive"))
      (node (ref "C6") (pin "1") (pinfunction "1_1") (pintype "passive"))
      (node (ref "C7") (pin "1") (pinfunction "1_1") (pintype "passive"))
      (node (ref "C8") (pin "1") (pinfunction "1_1") (pintype "passive"))
      (node (ref "C9") (pin "1") (pinfunction "1_1") (pintype "passive"))
      (node (ref "OMNIBUS") (pin "AA2") (pinfunction "1_AA2") (pintype "bidirectional"))
      (node (ref "OMNIBUS") (pin "BA2") (pinfunction "1_BA2") (pintype "bidirectional"))
      (node (ref "OMNIBUS") (pin "CA2") (pinfunction "1_CA2") (pintype "bidirectional"))
      (node (ref "R10") (pin "2") (pinfunction "2_2") (pintype "passive"))
      (node (ref "R12") (pin "1") (pinfunction "A_1") (pintype "passive"))
      (node (ref "R19") (pin "2") (pinfunction "2_2") (pintype "passive"))
      (node (ref "R2") (pin "1") (pinfunction "1_1") (pintype "passive"))
      (node (ref "R21") (pin "2") (pinfunction "2_2") (pintype "passive"))
      (node (ref "R22") (pin "2") (pinfunction "2_2") (pintype "passive"))
      (node (ref "R24") (pin "2") (pinfunction "2_2") (pintype "passive"))
      (node (ref "R26") (pin "2") (pinfunction "2_2") (pintype "passive"))
      (node (ref "R28") (pin "2") (pinfunction "2_2") (pintype "passive"))
      (node (ref "R29") (pin "2") (pinfunction "2_2") (pintype "passive"))
      (node (ref "R32") (pin "2") (pinfunction "2_2") (pintype "passive"))
      (node (ref "R33") (pin "2") (pinfunction "2_2") (pintype "passive"))
      (node (ref "R36") (pin "2") (pinfunction "2_2") (pintype "passive"))
      (node (ref "R38") (pin "2") (pinfunction "2_2") (pintype "passive"))
      (node (ref "R4") (pin "1") (pinfunction "A_1") (pintype "passive"))
      (node (ref "R40") (pin "2") (pinfunction "2_2") (pintype "passive"))
      (node (ref "R42") (pin "2") (pinfunction "2_2") (pintype "passive"))
      (node (ref "R43") (pin "2") (pinfunction "2_2") (pintype "passive"))
      (node (ref "R46") (pin "2") (pinfunction "2_2") (pintype "passive"))
      (node (ref "R48") (pin "2") (pinfunction "2_2") (pintype "passive"))
      (node (ref "R50") (pin "2") (pinfunction "2_2") (pintype "passive"))
      (node (ref "R52") (pin "2") (pinfunction "2_2") (pintype "passive"))
      (node (ref "R54") (pin "2") (pinfunction "2_2") (pintype "passive"))
      (node (ref "R8") (pin "2") (pinfunction "2_2") (pintype "passive"))
      (node (ref "R9") (pin "2") (pinfunction "2_2") (pintype "passive"))
    )
    (net (code "161") (name "WRITE") (class "Default")
      (node (ref "E28") (pin "5") (pinfunction "I5_5") (pintype "input"))
      (node (ref "E39") (pin "9") (pinfunction "I0_9") (pintype "input"))
      (node (ref "E41") (pin "1") (pinfunction "CLR_1") (pintype "input"))
      (node (ref "E41") (pin "9") (pinfunction "Q_9") (pintype "output"))
      (node (ref "E45") (pin "10") (pinfunction "I1_10") (pintype "input"))
      (node (ref "E50") (pin "1") (pinfunction "I0_1") (pintype "input"))
      (node (ref "E50") (pin "2") (pinfunction "I1_2") (pintype "input"))
      (node (ref "F") (pin "F1") (pinfunction "P_F1") (pintype "passive"))
    )
    (net (code "162") (name "WRT_CLK_DATA") (class "Default")
      (node (ref "E27") (pin "11") (pinfunction "O_11") (pintype "output"))
      (node (ref "E44") (pin "1") (pinfunction "I0_1") (pintype "input"))
      (node (ref "E44") (pin "2") (pinfunction "I1_2") (pintype "input"))
    )
    (net (code "163") (name "WRT_CMD") (class "Default")
      (node (ref "E30") (pin "11") (pinfunction "I0_11") (pintype "input"))
      (node (ref "E33") (pin "11") (pinfunction "O_11") (pintype "output"))
      (node (ref "E36") (pin "5") (pinfunction "I_5") (pintype "input"))
      (node (ref "E38") (pin "10") (pinfunction "B_10") (pintype "input"))
      (node (ref "E41") (pin "12") (pinfunction "D_12") (pintype "input"))
    )
    (net (code "164") (name "WRT_LOCK_OUT") (class "Default")
      (node (ref "E35") (pin "6") (pinfunction "O_6") (pintype "output"))
      (node (ref "E50") (pin "6") (pinfunction "I0_6") (pintype "input"))
    )
    (net (code "165") (name "WRT_SHFT_CRC") (class "Default")
      (node (ref "E40") (pin "1") (pinfunction "O_1") (pintype "output"))
      (node (ref "E40") (pin "12") (pinfunction "I1_12") (pintype "input"))
    )
    (net (code "166") (name "WRT_SYNC_BIT") (class "Default")
      (node (ref "E27") (pin "10") (pinfunction "I1_10") (pintype "input"))
      (node (ref "E37") (pin "5") (pinfunction "Q_5") (pintype "output"))
    )
    (net (code "167") (name "unconnected-(E1A-QA-Pad14)") (class "Default")
      (node (ref "E1") (pin "14") (pinfunction "QA_14") (pintype "output"))
    )
    (net (code "168") (name "unconnected-(E1A-QB-Pad13)") (class "Default")
      (node (ref "E1") (pin "13") (pinfunction "QB_13") (pintype "output"))
    )
    (net (code "169") (name "unconnected-(E1A-QC-Pad12)") (class "Default")
      (node (ref "E1") (pin "12") (pinfunction "QC_12") (pintype "output"))
    )
    (net (code "170") (name "unconnected-(E1A-QD-Pad11)") (class "Default")
      (node (ref "E1") (pin "11") (pinfunction "QD_11") (pintype "output"))
    )
    (net (code "171") (name "unconnected-(E2A-QC-Pad12)") (class "Default")
      (node (ref "E2") (pin "12") (pinfunction "QC_12") (pintype "output"))
    )
    (net (code "172") (name "unconnected-(E2A-RCO-Pad15)") (class "Default")
      (node (ref "E2") (pin "15") (pinfunction "RCO_15") (pintype "output"))
    )
    (net (code "173") (name "unconnected-(E3A-QA-Pad14)") (class "Default")
      (node (ref "E3") (pin "14") (pinfunction "QA_14") (pintype "output"))
    )
    (net (code "174") (name "unconnected-(E3A-QB-Pad13)") (class "Default")
      (node (ref "E3") (pin "13") (pinfunction "QB_13") (pintype "output"))
    )
    (net (code "175") (name "unconnected-(E3A-QC-Pad12)") (class "Default")
      (node (ref "E3") (pin "12") (pinfunction "QC_12") (pintype "output"))
    )
    (net (code "176") (name "unconnected-(E3A-QD-Pad11)") (class "Default")
      (node (ref "E3") (pin "11") (pinfunction "QD_11") (pintype "output"))
    )
    (net (code "177") (name "unconnected-(E4A-QA-Pad14)") (class "Default")
      (node (ref "E4") (pin "14") (pinfunction "QA_14") (pintype "output"))
    )
    (net (code "178") (name "unconnected-(E4A-QB-Pad13)") (class "Default")
      (node (ref "E4") (pin "13") (pinfunction "QB_13") (pintype "output"))
    )
    (net (code "179") (name "unconnected-(E4A-QC-Pad12)") (class "Default")
      (node (ref "E4") (pin "12") (pinfunction "QC_12") (pintype "output"))
    )
    (net (code "180") (name "unconnected-(E5A-QA-Pad14)") (class "Default")
      (node (ref "E5") (pin "14") (pinfunction "QA_14") (pintype "output"))
    )
    (net (code "181") (name "unconnected-(E5A-QB-Pad13)") (class "Default")
      (node (ref "E5") (pin "13") (pinfunction "QB_13") (pintype "output"))
    )
    (net (code "182") (name "unconnected-(E5A-QC-Pad12)") (class "Default")
      (node (ref "E5") (pin "12") (pinfunction "QC_12") (pintype "output"))
    )
    (net (code "183") (name "unconnected-(E5A-QD-Pad11)") (class "Default")
      (node (ref "E5") (pin "11") (pinfunction "QD_11") (pintype "output"))
    )
    (net (code "184") (name "unconnected-(E6A-QA-Pad14)") (class "Default")
      (node (ref "E6") (pin "14") (pinfunction "QA_14") (pintype "output"))
    )
    (net (code "185") (name "unconnected-(E6A-QB-Pad13)") (class "Default")
      (node (ref "E6") (pin "13") (pinfunction "QB_13") (pintype "output"))
    )
    (net (code "186") (name "unconnected-(E6A-QC-Pad12)") (class "Default")
      (node (ref "E6") (pin "12") (pinfunction "QC_12") (pintype "output"))
    )
    (net (code "187") (name "unconnected-(E6A-QD-Pad11)") (class "Default")
      (node (ref "E6") (pin "11") (pinfunction "QD_11") (pintype "output"))
    )
    (net (code "188") (name "unconnected-(E19A-Q-Pad5)") (class "Default")
      (node (ref "E19") (pin "5") (pinfunction "Q_5") (pintype "output"))
    )
    (net (code "189") (name "unconnected-(E19B-~{Q}-Pad8)") (class "Default")
      (node (ref "E19") (pin "8") (pinfunction "~{Q}_8") (pintype "output"))
    )
    (net (code "190") (name "unconnected-(E20A-~{Q}-Pad6)") (class "Default")
      (node (ref "E20") (pin "6") (pinfunction "~{Q}_6") (pintype "output"))
    )
    (net (code "191") (name "unconnected-(E28A-I9-Pad9)") (class "Default")
      (node (ref "E28") (pin "9") (pinfunction "I9_9") (pintype "passive"))
    )
    (net (code "192") (name "unconnected-(E31A-1Y2-Pad5)") (class "Default")
      (node (ref "E31") (pin "5") (pinfunction "1Y2_5") (pintype "output"))
    )
    (net (code "193") (name "unconnected-(E31A-1Y3-Pad4)") (class "Default")
      (node (ref "E31") (pin "4") (pinfunction "1Y3_4") (pintype "output"))
    )
    (net (code "194") (name "unconnected-(E38A-Q-Pad13)") (class "Default")
      (node (ref "E38") (pin "13") (pinfunction "Q_13") (pintype "output"))
    )
    (net (code "195") (name "unconnected-(E38B-Q-Pad5)") (class "Default")
      (node (ref "E38") (pin "5") (pinfunction "Q_5") (pintype "output"))
    )
    (net (code "196") (name "unconnected-(E43A-Q-Pad13)") (class "Default")
      (node (ref "E43") (pin "13") (pinfunction "Q_13") (pintype "output"))
    )
    (net (code "197") (name "unconnected-(E43B-Q-Pad5)") (class "Default")
      (node (ref "E43") (pin "5") (pinfunction "Q_5") (pintype "output"))
    )
    (net (code "198") (name "unconnected-(E47A-A<B_O-Pad7)") (class "Default")
      (node (ref "E47") (pin "7") (pinfunction "A<B_O_7") (pintype "output"))
    )
    (net (code "199") (name "unconnected-(E47A-A>B_O-Pad5)") (class "Default")
      (node (ref "E47") (pin "5") (pinfunction "A>B_O_5") (pintype "output"))
    )
    (net (code "200") (name "unconnected-(TP1-P-PadP$1)") (class "Default")
      (node (ref "TP1") (pin "P$1") (pinfunction "P_P$1") (pintype "passive"))
    )
    (net (code "201") (name "unconnected-(W1-Pad1)") (class "Default")
      (node (ref "W1") (pin "1") (pinfunction "1_1") (pintype "passive"))
    )
    (net (code "202") (name "unconnected-(W1-Pad2)") (class "Default")
      (node (ref "W1") (pin "2") (pinfunction "2_2") (pintype "passive"))
    )
    (net (code "203") (name "unconnected-(W2-Pad1)") (class "Default")
      (node (ref "W2") (pin "1") (pinfunction "1_1") (pintype "passive"))
    )
    (net (code "204") (name "unconnected-(W2-Pad2)") (class "Default")
      (node (ref "W2") (pin "2") (pinfunction "2_2") (pintype "passive"))
    )
    (net (code "205") (name "~{6RK3_OK}") (class "Default")
      (node (ref "E13") (pin "9") (pinfunction "I1_9") (pintype "input"))
      (node (ref "E5") (pin "9") (pinfunction "LD_9") (pintype "input"))
      (node (ref "E6") (pin "9") (pinfunction "LD_9") (pintype "input"))
      (node (ref "E9") (pin "8") (pinfunction "O_8") (pintype "output"))
    )
    (net (code "206") (name "~{12TH_CARRY}") (class "Default")
      (node (ref "E10") (pin "8") (pinfunction "O_8") (pintype "output"))
      (node (ref "E11") (pin "5") (pinfunction "I_5") (pintype "input"))
      (node (ref "E2") (pin "9") (pinfunction "LD_9") (pintype "input"))
      (node (ref "R1") (pin "1") (pinfunction "1_1") (pintype "passive"))
    )
    (net (code "207") (name "~{16TH_BIT}") (class "Default")
      (node (ref "E11") (pin "11") (pinfunction "I_11") (pintype "input"))
      (node (ref "E12") (pin "11") (pinfunction "O_11") (pintype "output"))
      (node (ref "E21") (pin "11") (pinfunction "CLK_11") (pintype "input"))
      (node (ref "E22") (pin "3") (pinfunction "CLK_3") (pintype "input"))
    )
    (net (code "208") (name "~{B_WRT_CLK}") (class "Default")
      (node (ref "E10") (pin "13") (pinfunction "I2_13") (pintype "input"))
      (node (ref "E29") (pin "6") (pinfunction "I1_6") (pintype "input"))
      (node (ref "E35") (pin "12") (pinfunction "O_12") (pintype "output"))
      (node (ref "E37") (pin "3") (pinfunction "CLK_3") (pintype "input"))
      (node (ref "E40") (pin "3") (pinfunction "I1_3") (pintype "input"))
    )
    (net (code "209") (name "~{CHECK_HEADER_CMD}") (class "Default")
      (node (ref "E19") (pin "2") (pinfunction "D_2") (pintype "input"))
      (node (ref "E32") (pin "8") (pinfunction "O_8") (pintype "output"))
    )
    (net (code "210") (name "~{CLR_ALL}") (class "Default")
      (node (ref "E") (pin "H1") (pinfunction "P_H1") (pintype "passive"))
      (node (ref "E10") (pin "4") (pinfunction "I1_4") (pintype "input"))
      (node (ref "E16") (pin "5") (pinfunction "I1_5") (pintype "input"))
      (node (ref "E25") (pin "5") (pinfunction "I1_5") (pintype "input"))
      (node (ref "E5") (pin "1") (pinfunction "CLR_1") (pintype "input"))
      (node (ref "E6") (pin "1") (pinfunction "CLR_1") (pintype "input"))
    )
    (net (code "211") (name "~{CLR_CNTRS}") (class "Default")
      (node (ref "E1") (pin "1") (pinfunction "CLR_1") (pintype "input"))
      (node (ref "E11") (pin "4") (pinfunction "O_4") (pintype "output"))
      (node (ref "E15") (pin "10") (pinfunction "PRE_10") (pintype "input"))
      (node (ref "E2") (pin "1") (pinfunction "CLR_1") (pintype "input"))
      (node (ref "E3") (pin "1") (pinfunction "CLR_1") (pintype "input"))
      (node (ref "E4") (pin "1") (pinfunction "CLR_1") (pintype "input"))
      (node (ref "F") (pin "S1") (pinfunction "P_S1") (pintype "passive"))
    )
    (net (code "212") (name "~{CLR_DRIVE_CMD}") (class "Default")
      (node (ref "E45") (pin "13") (pinfunction "I1_13") (pintype "input"))
      (node (ref "E9") (pin "11") (pinfunction "I_11") (pintype "input"))
      (node (ref "F") (pin "B2") (pinfunction "P_B2") (pintype "passive"))
    )
    (net (code "213") (name "~{CLR_SECTOR_AD}") (class "Default")
      (node (ref "E") (pin "F1") (pinfunction "P_F1") (pintype "passive"))
      (node (ref "E46") (pin "16") (pinfunction "CLR_16") (pintype "input"))
    )
    (net (code "214") (name "~{CLR_STROBE}") (class "Default")
      (node (ref "E18") (pin "13") (pinfunction "CLR_13") (pintype "input"))
      (node (ref "E19") (pin "13") (pinfunction "CLR_13") (pintype "input"))
      (node (ref "E26") (pin "10") (pinfunction "O_10") (pintype "output"))
    )
    (net (code "215") (name "~{CRC_STATE}") (class "Default")
      (node (ref "E14") (pin "1") (pinfunction "I0_1") (pintype "input"))
      (node (ref "E21") (pin "4") (pinfunction "PRE_4") (pintype "input"))
      (node (ref "E21") (pin "6") (pinfunction "~{Q}_6") (pintype "output"))
      (node (ref "E33") (pin "5") (pinfunction "I1_5") (pintype "input"))
    )
    (net (code "216") (name "~{DATA8}") (class "Default")
      (node (ref "E52") (pin "6") (pinfunction "I0_6") (pintype "input"))
      (node (ref "OMNIBUS") (pin "DR1") (pinfunction "1_DR1") (pintype "bidirectional"))
    )
    (net (code "217") (name "~{DATA9}") (class "Default")
      (node (ref "E52") (pin "4") (pinfunction "I0_4") (pintype "input"))
      (node (ref "OMNIBUS") (pin "DS1") (pinfunction "1_DS1") (pintype "bidirectional"))
    )
    (net (code "218") (name "~{DATA10}") (class "Default")
      (node (ref "E52") (pin "9") (pinfunction "I0_9") (pintype "input"))
      (node (ref "OMNIBUS") (pin "DU1") (pinfunction "1_DU1") (pintype "bidirectional"))
    )
    (net (code "219") (name "~{DATA11}") (class "Default")
      (node (ref "E52") (pin "11") (pinfunction "I0_11") (pintype "input"))
      (node (ref "OMNIBUS") (pin "DV1") (pinfunction "1_DV1") (pintype "bidirectional"))
    )
    (net (code "220") (name "~{DATA_CLR}") (class "Default")
      (node (ref "E10") (pin "5") (pinfunction "I2_5") (pintype "input"))
      (node (ref "E43") (pin "12") (pinfunction "~{Q}_12") (pintype "output"))
    )
    (net (code "221") (name "~{DATA_ENAB}") (class "Default")
      (node (ref "E") (pin "V1") (pinfunction "P_V1") (pintype "passive"))
      (node (ref "E52") (pin "10") (pinfunction "I1_10") (pintype "input"))
      (node (ref "E52") (pin "12") (pinfunction "I1_12") (pintype "input"))
      (node (ref "E52") (pin "5") (pinfunction "I1_5") (pintype "input"))
      (node (ref "E52") (pin "7") (pinfunction "I1_7") (pintype "input"))
    )
    (net (code "222") (name "~{DATA_IN}") (class "Default")
      (node (ref "E15") (pin "6") (pinfunction "~{Q}_6") (pintype "output"))
      (node (ref "F") (pin "R1") (pinfunction "P_R1") (pintype "passive"))
    )
    (net (code "223") (name "~{DATA_OUT_PL}") (class "Default")
      (node (ref "E27") (pin "13") (pinfunction "I1_13") (pintype "input"))
      (node (ref "E34") (pin "6") (pinfunction "O_6") (pintype "output"))
    )
    (net (code "224") (name "~{DATA_STATE}") (class "Default")
      (node (ref "E22") (pin "4") (pinfunction "PRE_4") (pintype "input"))
      (node (ref "E22") (pin "6") (pinfunction "~{Q}_6") (pintype "output"))
      (node (ref "E29") (pin "5") (pinfunction "I0_5") (pintype "input"))
      (node (ref "F") (pin "P1") (pinfunction "P_P1") (pintype "passive"))
    )
    (net (code "225") (name "~{DSK_ACKNOWLEDGE}") (class "Default")
      (node (ref "E16") (pin "2") (pinfunction "I1_2") (pintype "input"))
      (node (ref "E42") (pin "7") (pinfunction "I1_7") (pintype "input"))
      (node (ref "J2") (pin "H") (pinfunction "P_H") (pintype "passive"))
    )
    (net (code "226") (name "~{DSK_CAPACITY_EX}") (class "Default")
      (node (ref "F") (pin "C1") (pinfunction "P_C1") (pintype "passive"))
      (node (ref "J2") (pin "C") (pinfunction "P_C") (pintype "passive"))
    )
    (net (code "227") (name "~{DSK_CYL_AD1}") (class "Default")
      (node (ref "E") (pin "S1") (pinfunction "P_S1") (pintype "passive"))
      (node (ref "J2") (pin "Y") (pinfunction "P_Y") (pintype "passive"))
    )
    (net (code "228") (name "~{DSK_CYL_AD2}") (class "Default")
      (node (ref "E") (pin "K2") (pinfunction "P_K2") (pintype "passive"))
      (node (ref "J2") (pin "SS") (pinfunction "P_SS") (pintype "passive"))
    )
    (net (code "229") (name "~{DSK_CYL_AD4}") (class "Default")
      (node (ref "E") (pin "H2") (pinfunction "P_H2") (pintype "passive"))
      (node (ref "J2") (pin "U") (pinfunction "P_U") (pintype "passive"))
    )
    (net (code "230") (name "~{DSK_CYL_AD8}") (class "Default")
      (node (ref "E") (pin "T1") (pinfunction "P_T1") (pintype "passive"))
      (node (ref "J2") (pin "UU") (pinfunction "P_UU") (pintype "passive"))
    )
    (net (code "231") (name "~{DSK_CYL_AD16}") (class "Default")
      (node (ref "E") (pin "C2") (pinfunction "P_C2") (pintype "passive"))
      (node (ref "J2") (pin "MM") (pinfunction "P_MM") (pintype "passive"))
    )
    (net (code "232") (name "~{DSK_CYL_AD32}") (class "Default")
      (node (ref "E") (pin "J2") (pinfunction "P_J2") (pintype "passive"))
      (node (ref "J2") (pin "CC") (pinfunction "P_CC") (pintype "passive"))
    )
    (net (code "233") (name "~{DSK_CYL_AD64}") (class "Default")
      (node (ref "E") (pin "B2") (pinfunction "P_B2") (pintype "passive"))
      (node (ref "J2") (pin "PP") (pinfunction "P_PP") (pintype "passive"))
    )
    (net (code "234") (name "~{DSK_CYL_AD128}") (class "Default")
      (node (ref "E") (pin "E2") (pinfunction "P_E2") (pintype "passive"))
      (node (ref "J2") (pin "HH") (pinfunction "P_HH") (pintype "passive"))
    )
    (net (code "235") (name "~{DSK_DATA_IN}") (class "Default")
      (node (ref "E54") (pin "5") (pinfunction "I1_5") (pintype "input"))
      (node (ref "J1") (pin "D") (pinfunction "P_D") (pintype "passive"))
      (node (ref "R31") (pin "2") (pinfunction "2_2") (pintype "passive"))
      (node (ref "R32") (pin "1") (pinfunction "1_1") (pintype "passive"))
    )
    (net (code "236") (name "~{DSK_DRIVE0}") (class "Default")
      (node (ref "E") (pin "D2") (pinfunction "P_D2") (pintype "passive"))
      (node (ref "J2") (pin "AA") (pinfunction "P_AA") (pintype "passive"))
    )
    (net (code "237") (name "~{DSK_DRIVE1}") (class "Default")
      (node (ref "E") (pin "R1") (pinfunction "P_R1") (pintype "passive"))
      (node (ref "J2") (pin "W") (pinfunction "P_W") (pintype "passive"))
    )
    (net (code "238") (name "~{DSK_DRIVE2}") (class "Default")
      (node (ref "E") (pin "P1") (pinfunction "P_P1") (pintype "passive"))
      (node (ref "J2") (pin "S") (pinfunction "P_S") (pintype "passive"))
    )
    (net (code "239") (name "~{DSK_DRIVE3}") (class "Default")
      (node (ref "E") (pin "N1") (pinfunction "P_N1") (pintype "passive"))
      (node (ref "J2") (pin "M") (pinfunction "P_M") (pintype "passive"))
    )
    (net (code "240") (name "~{DSK_FILE_RDY}") (class "Default")
      (node (ref "E54") (pin "6") (pinfunction "I0_6") (pintype "input"))
      (node (ref "F") (pin "B1") (pinfunction "P_B1") (pintype "passive"))
      (node (ref "J1") (pin "V") (pinfunction "P_V") (pintype "passive"))
      (node (ref "R33") (pin "1") (pinfunction "1_1") (pintype "passive"))
      (node (ref "R34") (pin "2") (pinfunction "2_2") (pintype "passive"))
    )
    (net (code "241") (name "~{DSK_HEAD_SEL1}") (class "Default")
      (node (ref "E48") (pin "5") (pinfunction "O_5") (pintype "open_collector"))
      (node (ref "J1") (pin "X") (pinfunction "P_X") (pintype "passive"))
      (node (ref "R47") (pin "2") (pinfunction "2_2") (pintype "passive"))
      (node (ref "R48") (pin "1") (pinfunction "1_1") (pintype "passive"))
    )
    (net (code "242") (name "~{DSK_INDEX_MK}") (class "Default")
      (node (ref "E53") (pin "11") (pinfunction "I0_11") (pintype "input"))
      (node (ref "J1") (pin "Z") (pinfunction "P_Z") (pintype "passive"))
      (node (ref "R27") (pin "2") (pinfunction "2_2") (pintype "passive"))
      (node (ref "R28") (pin "1") (pinfunction "1_1") (pintype "passive"))
    )
    (net (code "243") (name "~{DSK_RDY_S-R-W}") (class "Default")
      (node (ref "E") (pin "L2") (pinfunction "P_L2") (pintype "passive"))
      (node (ref "J2") (pin "EE") (pinfunction "P_EE") (pintype "passive"))
    )
    (net (code "244") (name "~{DSK_RD_CLK}") (class "Default")
      (node (ref "E54") (pin "9") (pinfunction "I0_9") (pintype "input"))
      (node (ref "J1") (pin "F") (pinfunction "P_F") (pintype "passive"))
      (node (ref "R29") (pin "1") (pinfunction "1_1") (pintype "passive"))
      (node (ref "R30") (pin "2") (pinfunction "2_2") (pintype "passive"))
    )
    (net (code "245") (name "~{DSK_READ}") (class "Default")
      (node (ref "E49") (pin "3") (pinfunction "O_3") (pintype "open_collector"))
      (node (ref "J1") (pin "L") (pinfunction "P_L") (pintype "passive"))
      (node (ref "R45") (pin "2") (pinfunction "2_2") (pintype "passive"))
      (node (ref "R46") (pin "1") (pinfunction "1_1") (pintype "passive"))
    )
    (net (code "246") (name "~{DSK_RESTORE}") (class "Default")
      (node (ref "E49") (pin "5") (pinfunction "O_5") (pintype "open_collector"))
      (node (ref "J2") (pin "P") (pinfunction "P_P") (pintype "passive"))
      (node (ref "R20") (pin "2") (pinfunction "2_2") (pintype "passive"))
      (node (ref "R21") (pin "1") (pinfunction "1_1") (pintype "passive"))
    )
    (net (code "247") (name "~{DSK_SEC1}") (class "Default")
      (node (ref "E53") (pin "9") (pinfunction "I0_9") (pintype "input"))
      (node (ref "J1") (pin "DD") (pinfunction "P_DD") (pintype "passive"))
      (node (ref "R39") (pin "2") (pinfunction "2_2") (pintype "passive"))
      (node (ref "R40") (pin "1") (pinfunction "1_1") (pintype "passive"))
    )
    (net (code "248") (name "~{DSK_SEC2}") (class "Default")
      (node (ref "E42") (pin "4") (pinfunction "I0_4") (pintype "input"))
      (node (ref "J2") (pin "K") (pinfunction "P_K") (pintype "passive"))
    )
    (net (code "249") (name "~{DSK_SEC4}") (class "Default")
      (node (ref "E53") (pin "4") (pinfunction "I0_4") (pintype "input"))
      (node (ref "J1") (pin "FF") (pinfunction "P_FF") (pintype "passive"))
      (node (ref "R37") (pin "2") (pinfunction "2_2") (pintype "passive"))
      (node (ref "R38") (pin "1") (pinfunction "1_1") (pintype "passive"))
    )
    (net (code "250") (name "~{DSK_SEC8}") (class "Default")
      (node (ref "E53") (pin "6") (pinfunction "I0_6") (pintype "input"))
      (node (ref "J1") (pin "LL") (pinfunction "P_LL") (pintype "passive"))
      (node (ref "R35") (pin "2") (pinfunction "2_2") (pintype "passive"))
      (node (ref "R36") (pin "1") (pinfunction "1_1") (pintype "passive"))
    )
    (net (code "251") (name "~{DSK_SECTOR_MK}") (class "Default")
      (node (ref "E54") (pin "12") (pinfunction "I1_12") (pintype "input"))
      (node (ref "J1") (pin "T") (pinfunction "P_T") (pintype "passive"))
      (node (ref "R41") (pin "2") (pinfunction "2_2") (pintype "passive"))
      (node (ref "R42") (pin "1") (pinfunction "1_1") (pintype "passive"))
    )
    (net (code "252") (name "~{DSK_SEEK_FAIL}") (class "Default")
      (node (ref "E") (pin "A2") (pinfunction "P_A2") (pintype "passive"))
      (node (ref "J2") (pin "E") (pinfunction "P_E") (pintype "passive"))
    )
    (net (code "253") (name "~{DSK_STROBE}") (class "Default")
      (node (ref "E48") (pin "3") (pinfunction "O_3") (pintype "open_collector"))
      (node (ref "J1") (pin "RR") (pinfunction "P_RR") (pintype "passive"))
      (node (ref "R49") (pin "2") (pinfunction "2_2") (pintype "passive"))
      (node (ref "R50") (pin "1") (pinfunction "1_1") (pintype "passive"))
    )
    (net (code "254") (name "~{DSK_WRT-ERASE_GATE}") (class "Default")
      (node (ref "E50") (pin "3") (pinfunction "O_3") (pintype "open_collector"))
      (node (ref "J1") (pin "BB") (pinfunction "P_BB") (pintype "passive"))
      (node (ref "R53") (pin "2") (pinfunction "2_2") (pintype "passive"))
      (node (ref "R54") (pin "1") (pinfunction "1_1") (pintype "passive"))
    )
    (net (code "255") (name "~{DSK_WRT_CLK_DATA}") (class "Default")
      (node (ref "E44") (pin "3") (pinfunction "O_3") (pintype "open_collector"))
      (node (ref "J2") (pin "KK") (pinfunction "P_KK") (pintype "passive"))
      (node (ref "R10") (pin "1") (pinfunction "1_1") (pintype "passive"))
      (node (ref "R11") (pin "2") (pinfunction "2_2") (pintype "passive"))
    )
    (net (code "256") (name "~{DSK_WRT_PROTECT}") (class "Default")
      (node (ref "E50") (pin "5") (pinfunction "O_5") (pintype "open_collector"))
      (node (ref "J1") (pin "J") (pinfunction "P_J") (pintype "passive"))
      (node (ref "R51") (pin "2") (pinfunction "2_2") (pintype "passive"))
      (node (ref "R52") (pin "1") (pinfunction "1_1") (pintype "passive"))
    )
    (net (code "257") (name "~{DSK_WRT_STATUS}") (class "Default")
      (node (ref "E51") (pin "10") (pinfunction "I1_10") (pintype "input"))
      (node (ref "F") (pin "D2") (pinfunction "P_D2") (pintype "passive"))
      (node (ref "J1") (pin "R") (pinfunction "P_R") (pintype "passive"))
    )
    (net (code "258") (name "~{END_STATE}") (class "Default")
      (node (ref "E21") (pin "8") (pinfunction "~{Q}_8") (pintype "output"))
      (node (ref "F") (pin "D1") (pinfunction "P_D1") (pintype "passive"))
    )
    (net (code "259") (name "~{ERASE_DLY}") (class "Default")
      (node (ref "E25") (pin "2") (pinfunction "I1_2") (pintype "input"))
      (node (ref "E43") (pin "4") (pinfunction "~{Q}_4") (pintype "output"))
    )
    (net (code "260") (name "~{ERROR_CLR}") (class "Default")
      (node (ref "E25") (pin "4") (pinfunction "I0_4") (pintype "input"))
      (node (ref "F") (pin "E2") (pinfunction "P_E2") (pintype "passive"))
    )
    (net (code "261") (name "~{GO}") (class "Default")
      (node (ref "E18") (pin "4") (pinfunction "PRE_4") (pintype "input"))
      (node (ref "E9") (pin "2") (pinfunction "O_2") (pintype "output"))
    )
    (net (code "262") (name "~{HEADER_C}") (class "Default")
      (node (ref "E14") (pin "2") (pinfunction "I1_2") (pintype "input"))
      (node (ref "E20") (pin "10") (pinfunction "PRE_10") (pintype "input"))
      (node (ref "E20") (pin "8") (pinfunction "~{Q}_8") (pintype "output"))
    )
    (net (code "263") (name "~{HEADER_D}") (class "Default")
      (node (ref "E24") (pin "8") (pinfunction "~{Q}_8") (pintype "output"))
      (node (ref "E30") (pin "12") (pinfunction "I1_12") (pintype "input"))
    )
    (net (code "264") (name "~{HEADER_E}") (class "Default")
      (node (ref "E22") (pin "10") (pinfunction "PRE_10") (pintype "input"))
      (node (ref "E22") (pin "8") (pinfunction "~{Q}_8") (pintype "output"))
      (node (ref "E33") (pin "4") (pinfunction "I0_4") (pintype "input"))
    )
    (net (code "265") (name "~{HI_MAIN_SHFT}") (class "Default")
      (node (ref "E10") (pin "1") (pinfunction "I0_1") (pintype "input"))
      (node (ref "F") (pin "T2") (pinfunction "P_T2") (pintype "passive"))
    )
    (net (code "266") (name "~{IDLE}") (class "Default")
      (node (ref "E18") (pin "5") (pinfunction "Q_5") (pintype "output"))
      (node (ref "E21") (pin "13") (pinfunction "CLR_13") (pintype "input"))
      (node (ref "E35") (pin "11") (pinfunction "I_11") (pintype "input"))
      (node (ref "E41") (pin "13") (pinfunction "CLR_13") (pintype "input"))
      (node (ref "F") (pin "R2") (pinfunction "P_R2") (pintype "passive"))
    )
    (net (code "267") (name "~{INC_BRK_CNTR}") (class "Default")
      (node (ref "E13") (pin "4") (pinfunction "O_4") (pintype "output"))
      (node (ref "E5") (pin "2") (pinfunction "CLK_2") (pintype "input"))
      (node (ref "E6") (pin "2") (pinfunction "CLK_2") (pintype "input"))
    )
    (net (code "268") (name "~{INC_CNTRS}") (class "Default")
      (node (ref "E1") (pin "2") (pinfunction "CLK_2") (pintype "input"))
      (node (ref "E11") (pin "2") (pinfunction "O_2") (pintype "output"))
      (node (ref "E2") (pin "2") (pinfunction "CLK_2") (pintype "input"))
      (node (ref "E3") (pin "2") (pinfunction "CLK_2") (pintype "input"))
      (node (ref "E4") (pin "2") (pinfunction "CLK_2") (pintype "input"))
    )
    (net (code "269") (name "~{INH_12TH_BIT}") (class "Default")
      (node (ref "E14") (pin "12") (pinfunction "I0_12") (pintype "input"))
      (node (ref "E15") (pin "9") (pinfunction "Q_9") (pintype "output"))
      (node (ref "E17") (pin "12") (pinfunction "I0_12") (pintype "input"))
    )
    (net (code "270") (name "~{INSIDE_IN}") (class "Default")
      (node (ref "E45") (pin "2") (pinfunction "I1_2") (pintype "input"))
      (node (ref "OMNIBUS") (pin "DB1") (pinfunction "1_DB1") (pintype "bidirectional"))
      (node (ref "R9") (pin "1") (pinfunction "1_1") (pintype "passive"))
      (node (ref "TP2") (pin "P$1") (pinfunction "P_P$1") (pintype "passive"))
    )
    (net (code "271") (name "~{LAST_WORD_PL}") (class "Default")
      (node (ref "E11") (pin "9") (pinfunction "I_9") (pintype "input"))
      (node (ref "E12") (pin "8") (pinfunction "O_8") (pintype "output"))
      (node (ref "E21") (pin "3") (pinfunction "CLK_3") (pintype "input"))
    )
    (net (code "272") (name "~{LO_MAIN_SHFT}") (class "Default")
      (node (ref "E17") (pin "9") (pinfunction "I0_9") (pintype "input"))
      (node (ref "F") (pin "L1") (pinfunction "P_L1") (pintype "passive"))
    )
    (net (code "273") (name "~{MAIN}") (class "Default")
      (node (ref "E39") (pin "13") (pinfunction "I2_13") (pintype "input"))
      (node (ref "F") (pin "P2") (pinfunction "P_P2") (pintype "passive"))
    )
    (net (code "274") (name "~{OUTSIDE_CLK}") (class "Default")
      (node (ref "E45") (pin "5") (pinfunction "I1_5") (pintype "input"))
      (node (ref "OMNIBUS") (pin "DA1") (pinfunction "1_DA1") (pintype "bidirectional"))
      (node (ref "R8") (pin "1") (pinfunction "1_1") (pintype "passive"))
      (node (ref "TP3") (pin "P$1") (pinfunction "P_P$1") (pintype "passive"))
    )
    (net (code "275") (name "~{RD_CLK1}") (class "Default")
      (node (ref "E16") (pin "12") (pinfunction "I0_12") (pintype "input"))
      (node (ref "E30") (pin "8") (pinfunction "I0_8") (pintype "input"))
      (node (ref "E7") (pin "11") (pinfunction "I_11") (pintype "input"))
      (node (ref "E7") (pin "9") (pinfunction "I_9") (pintype "input"))
      (node (ref "E8") (pin "11") (pinfunction "O_11") (pintype "output"))
    )
    (net (code "276") (name "~{RD_CLK2}") (class "Default")
      (node (ref "E10") (pin "2") (pinfunction "I1_2") (pintype "input"))
      (node (ref "E15") (pin "3") (pinfunction "CLK_3") (pintype "input"))
      (node (ref "E7") (pin "6") (pinfunction "O_6") (pintype "output"))
    )
    (net (code "277") (name "~{RD_SHFT_DB}") (class "Default")
      (node (ref "E14") (pin "8") (pinfunction "O_8") (pintype "output"))
      (node (ref "F") (pin "S2") (pinfunction "P_S2") (pintype "passive"))
    )
    (net (code "278") (name "~{RD_SYNC_BIT}") (class "Default")
      (node (ref "E20") (pin "11") (pinfunction "CLK_11") (pintype "input"))
      (node (ref "E32") (pin "2") (pinfunction "I1_2") (pintype "input"))
      (node (ref "E8") (pin "8") (pinfunction "O_8") (pintype "output"))
    )
    (net (code "279") (name "~{READ_DATA_IN}") (class "Default")
      (node (ref "E15") (pin "4") (pinfunction "PRE_4") (pintype "input"))
      (node (ref "E35") (pin "4") (pinfunction "O_4") (pintype "output"))
    )
    (net (code "280") (name "~{READ_DLY}") (class "Default")
      (node (ref "E37") (pin "11") (pinfunction "CLK_11") (pintype "input"))
      (node (ref "E38") (pin "4") (pinfunction "~{Q}_4") (pintype "output"))
    )
    (net (code "281") (name "~{READ}") (class "Default")
      (node (ref "E37") (pin "9") (pinfunction "Q_9") (pintype "output"))
      (node (ref "E54") (pin "10") (pinfunction "I1_10") (pintype "input"))
      (node (ref "E54") (pin "4") (pinfunction "I0_4") (pintype "input"))
    )
    (net (code "282") (name "~{RESTORE}") (class "Default")
      (node (ref "E18") (pin "8") (pinfunction "~{Q}_8") (pintype "output"))
      (node (ref "E25") (pin "13") (pinfunction "I1_13") (pintype "input"))
    )
    (net (code "283") (name "~{SECTOR_MK}") (class "Default")
      (node (ref "E24") (pin "11") (pinfunction "CLK_11") (pintype "input"))
      (node (ref "E35") (pin "2") (pinfunction "O_2") (pintype "output"))
      (node (ref "E38") (pin "9") (pinfunction "A_9") (pintype "input"))
    )
    (net (code "284") (name "~{SECTOR_SEEK}") (class "Default")
      (node (ref "E24") (pin "6") (pinfunction "~{Q}_6") (pintype "output"))
      (node (ref "F") (pin "F2") (pinfunction "P_F2") (pintype "passive"))
    )
    (net (code "285") (name "~{SEEK}") (class "Default")
      (node (ref "E25") (pin "12") (pinfunction "I0_12") (pintype "input"))
      (node (ref "E31") (pin "12") (pinfunction "2Y3_12") (pintype "output"))
    )
    (net (code "286") (name "~{SET_HEADER_E}") (class "Default")
      (node (ref "E27") (pin "8") (pinfunction "O_8") (pintype "output"))
      (node (ref "E32") (pin "1") (pinfunction "I0_1") (pintype "input"))
    )
    (net (code "287") (name "~{SET_IDLE_PL}") (class "Default")
      (node (ref "E27") (pin "2") (pinfunction "I1_2") (pintype "input"))
      (node (ref "F") (pin "K1") (pinfunction "P_K1") (pintype "passive"))
    )
    (net (code "288") (name "~{SET_SECTOR_SEEK}") (class "Default")
      (node (ref "E24") (pin "4") (pinfunction "PRE_4") (pintype "input"))
      (node (ref "E27") (pin "6") (pinfunction "O_6") (pintype "output"))
    )
    (net (code "289") (name "~{SHFT_WRT_BUFF}") (class "Default")
      (node (ref "E14") (pin "11") (pinfunction "O_11") (pintype "output"))
      (node (ref "F") (pin "J2") (pinfunction "P_J2") (pintype "passive"))
    )
    (net (code "290") (name "~{SHIFT_CRC}") (class "Default")
      (node (ref "E40") (pin "13") (pinfunction "O_13") (pintype "output"))
      (node (ref "F") (pin "N1") (pinfunction "P_N1") (pintype "passive"))
    )
    (net (code "291") (name "~{SK{slash}CHK{slash}RD}") (class "Default")
      (node (ref "E31") (pin "9") (pinfunction "2Y0_9") (pintype "output"))
      (node (ref "E32") (pin "9") (pinfunction "I0_9") (pintype "input"))
    )
    (net (code "292") (name "~{SK{slash}CHK{slash}WRT}") (class "Default")
      (node (ref "E31") (pin "7") (pinfunction "1Y0_7") (pintype "output"))
      (node (ref "E32") (pin "10") (pinfunction "I1_10") (pintype "input"))
      (node (ref "E33") (pin "12") (pinfunction "I0_12") (pintype "input"))
    )
    (net (code "293") (name "~{SK{slash}RD}") (class "Default")
      (node (ref "E31") (pin "10") (pinfunction "2Y1_10") (pintype "output"))
      (node (ref "E34") (pin "9") (pinfunction "I0_9") (pintype "input"))
    )
    (net (code "294") (name "~{SK{slash}WRT}") (class "Default")
      (node (ref "E31") (pin "6") (pinfunction "1Y1_6") (pintype "output"))
      (node (ref "E33") (pin "13") (pinfunction "I1_13") (pintype "input"))
      (node (ref "E34") (pin "10") (pinfunction "I1_10") (pintype "input"))
      (node (ref "E34") (pin "11") (pinfunction "I2_11") (pintype "input"))
    )
    (net (code "295") (name "~{STATE_ENAB_A}") (class "Default")
      (node (ref "E23") (pin "4") (pinfunction "O_4") (pintype "output"))
      (node (ref "E30") (pin "9") (pinfunction "I1_9") (pintype "input"))
    )
    (net (code "296") (name "~{SYNC_DLY}") (class "Default")
      (node (ref "E37") (pin "2") (pinfunction "D_2") (pintype "input"))
      (node (ref "E38") (pin "12") (pinfunction "~{Q}_12") (pintype "output"))
    )
    (net (code "297") (name "~{WRITE}") (class "Default")
      (node (ref "E41") (pin "8") (pinfunction "~{Q}_8") (pintype "output"))
      (node (ref "E8") (pin "5") (pinfunction "I1_5") (pintype "input"))
    )
    (net (code "298") (name "~{WRT_CLK}") (class "Default")
      (node (ref "E27") (pin "12") (pinfunction "I0_12") (pintype "input"))
      (node (ref "E29") (pin "12") (pinfunction "I1_12") (pintype "input"))
      (node (ref "E36") (pin "11") (pinfunction "I_11") (pintype "input"))
      (node (ref "E39") (pin "8") (pinfunction "O_8") (pintype "output"))
    )
    (net (code "299") (name "~{WRT_CMD}") (class "Default")
      (node (ref "E36") (pin "6") (pinfunction "O_6") (pintype "output"))
      (node (ref "E39") (pin "3") (pinfunction "I0_3") (pintype "input"))
      (node (ref "E43") (pin "1") (pinfunction "A_1") (pintype "input"))
      (node (ref "E51") (pin "9") (pinfunction "I0_9") (pintype "input"))
      (node (ref "F") (pin "V2") (pinfunction "P_V2") (pintype "passive"))
    )
    (net (code "300") (name "~{WRT_LOCK_OUT}") (class "Default")
      (node (ref "E31") (pin "11") (pinfunction "2Y2_11") (pintype "output"))
      (node (ref "E32") (pin "13") (pinfunction "I1_13") (pintype "input"))
      (node (ref "E35") (pin "5") (pinfunction "I_5") (pintype "input"))
    )
    (net (code "301") (name "~{WRT_SYNC_BIT}") (class "Default")
      (node (ref "E34") (pin "13") (pinfunction "I2_13") (pintype "input"))
      (node (ref "E37") (pin "6") (pinfunction "~{Q}_6") (pintype "output"))
    )
  )
)
